# LJ_Mosfet_Power.net
KiCad netlist of a schematic drawn in Altium Designer
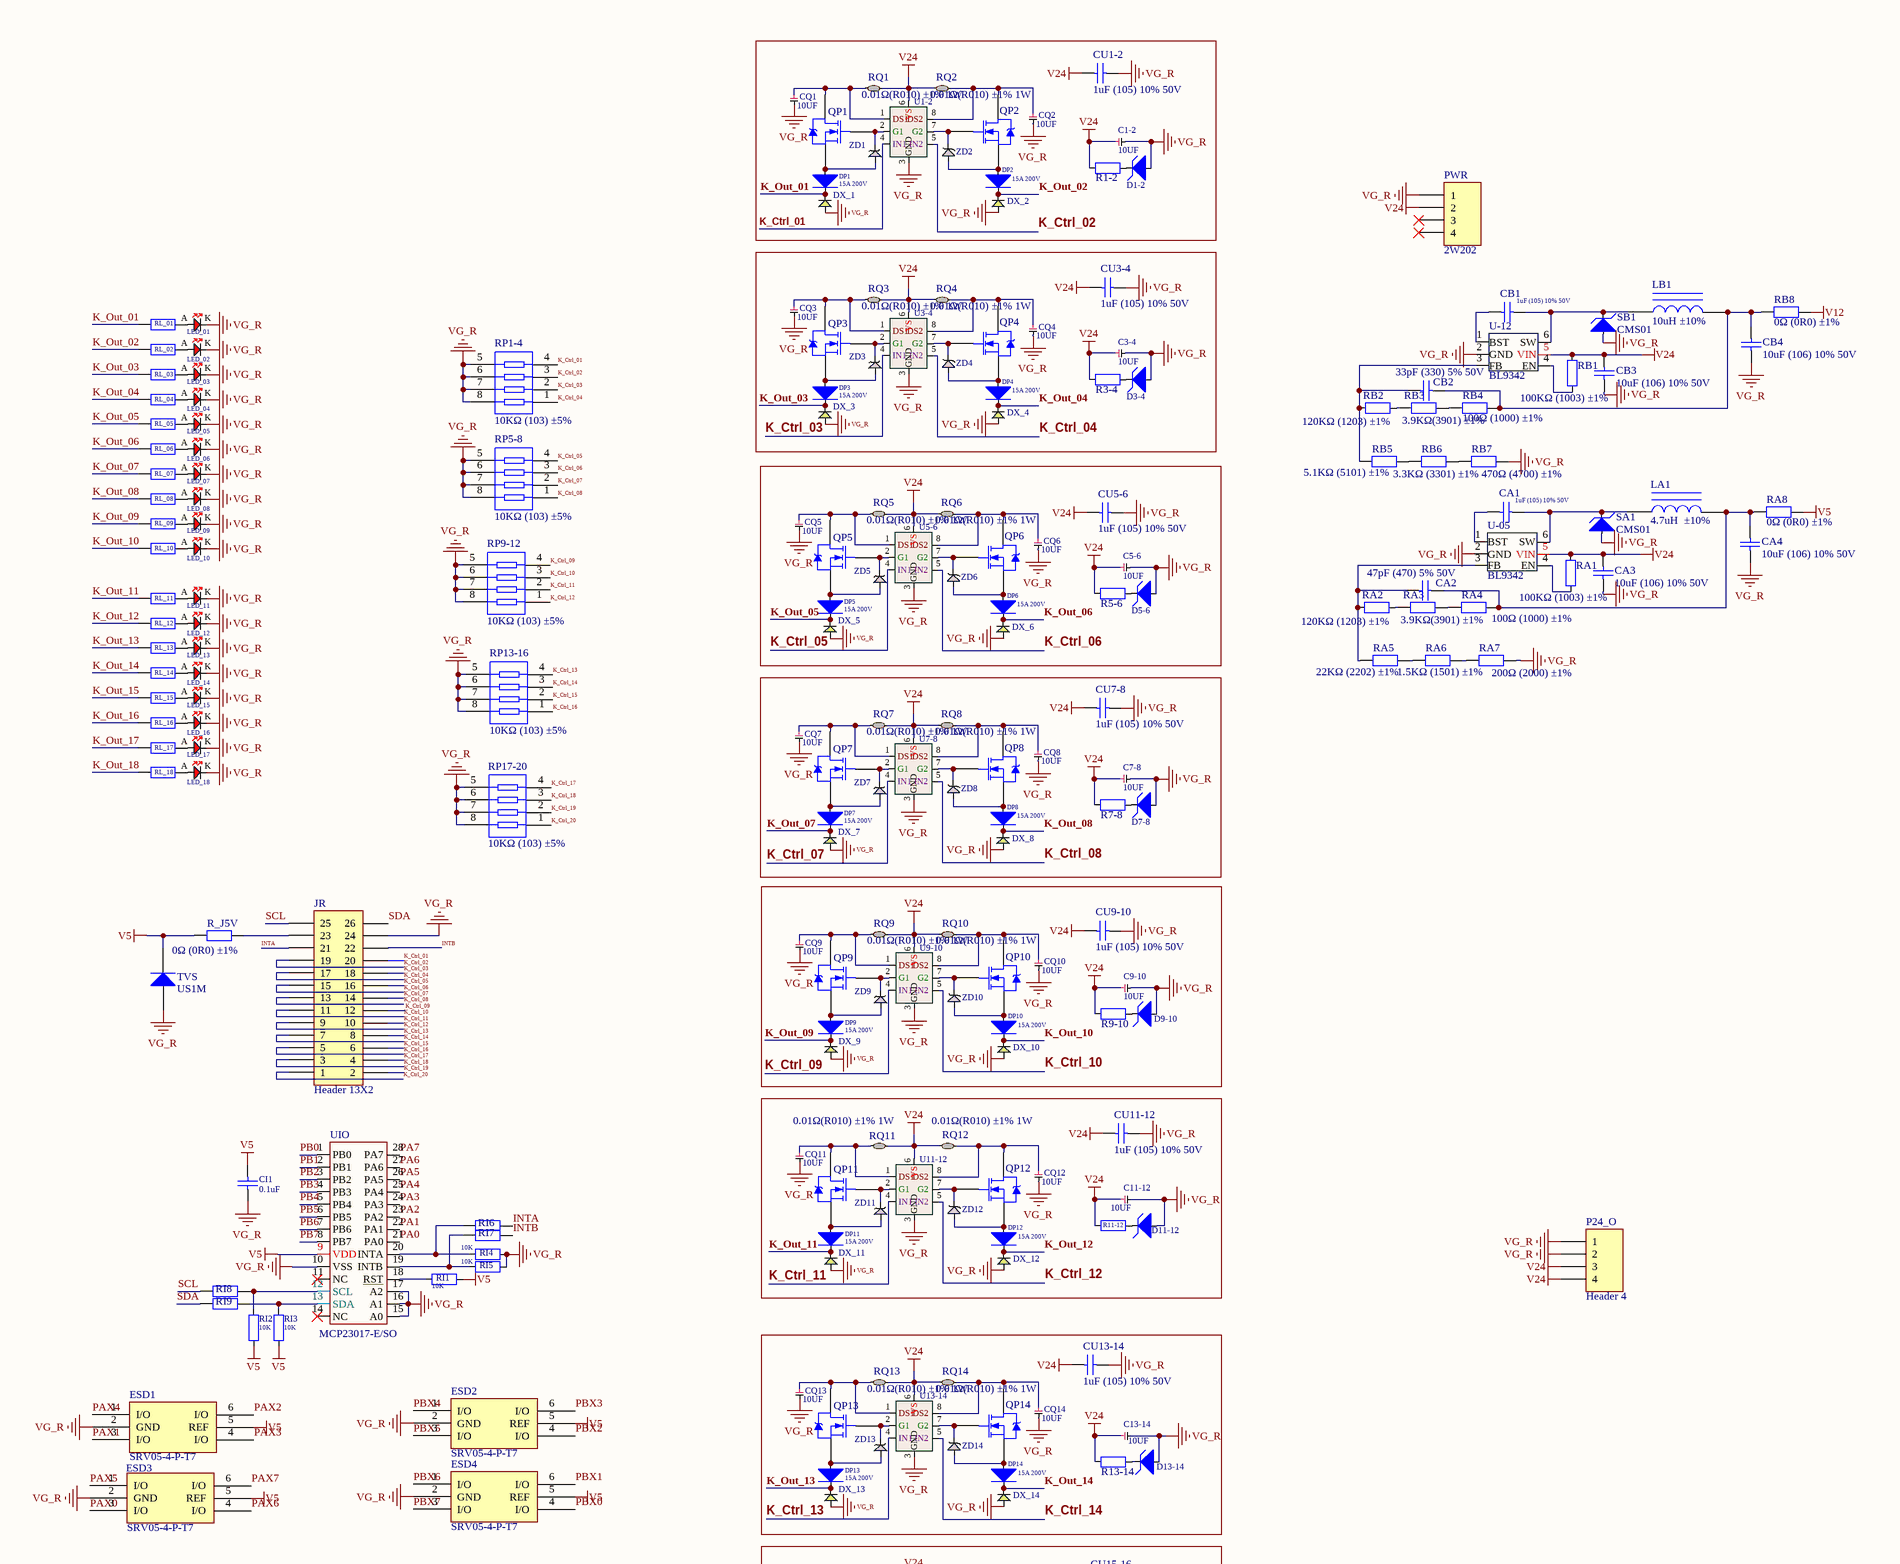
[diagram p0: LJ_Mosfet_Power.SchDoc, top left]
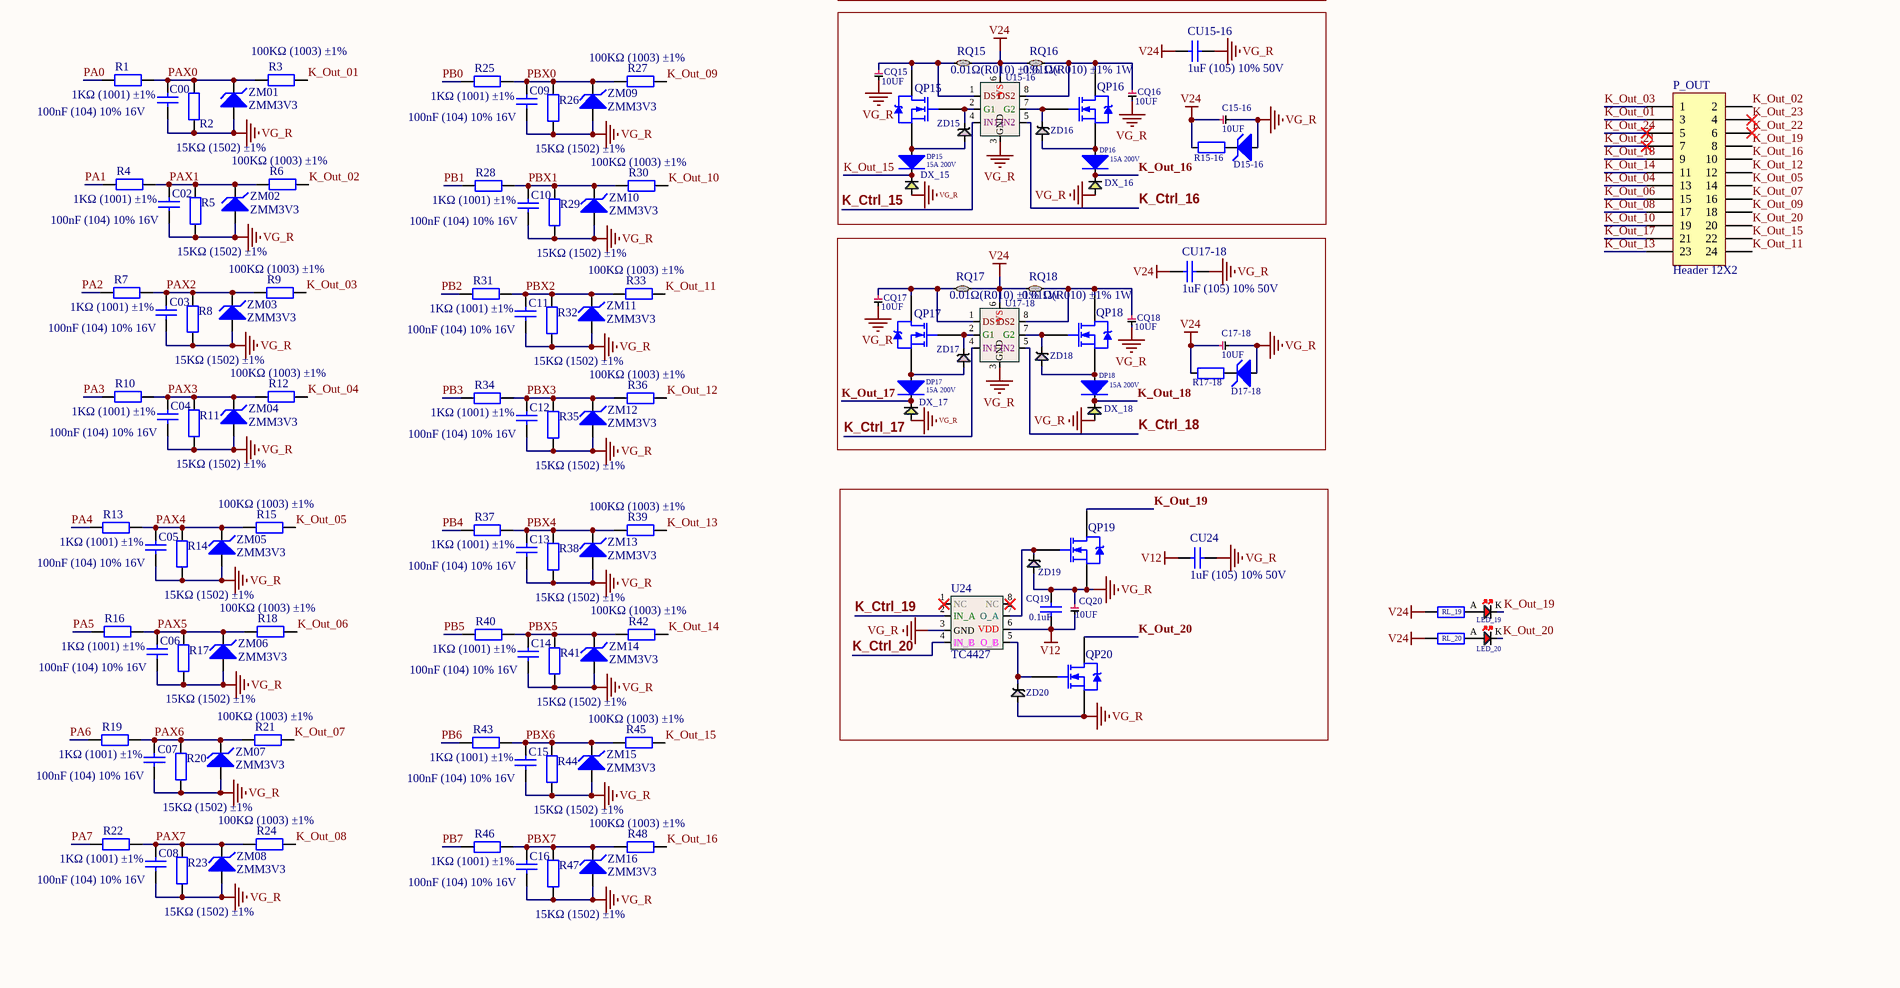
[diagram p1: LJ_Mosfet_Power.SchDoc, bottom left]
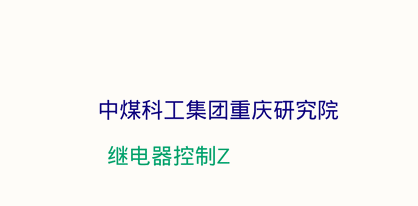
[diagram p2: LJ_Mosfet_Power.SchDoc, bottom right]

(export (version "E")
  (design (tool "Eeschema 10.0.6"))
  (components
    (comp (ref "C00")
      (value "100nF (104) 10% 16V")
      (footprint "0402_C")
      (description "贴片电容")
      (libsource (lib "Miscellaneous Devices LC") (part "0402 100nF (104) 10% 16V"))
    )
    (comp (ref "C1-2")
      (value "10UF")
      (footprint "C1210")
      (description "贴片电容")
      (libsource (lib "Active_crystal") (part "C"))
    )
    (comp (ref "C02")
      (value "100nF (104) 10% 16V")
      (footprint "0402_C")
      (description "贴片电容")
      (libsource (lib "Miscellaneous Devices LC") (part "0402 100nF (104) 10% 16V"))
    )
    (comp (ref "C03")
      (value "100nF (104) 10% 16V")
      (footprint "0402_C")
      (description "贴片电容")
      (libsource (lib "Miscellaneous Devices LC") (part "0402 100nF (104) 10% 16V"))
    )
    (comp (ref "C3-4")
      (value "10UF")
      (footprint "C1210")
      (description "贴片电容")
      (libsource (lib "Active_crystal") (part "C"))
    )
    (comp (ref "C04")
      (value "100nF (104) 10% 16V")
      (footprint "0402_C")
      (description "贴片电容")
      (libsource (lib "Miscellaneous Devices LC") (part "0402 100nF (104) 10% 16V"))
    )
    (comp (ref "C05")
      (value "100nF (104) 10% 16V")
      (footprint "0402_C")
      (description "贴片电容")
      (libsource (lib "Miscellaneous Devices LC") (part "0402 100nF (104) 10% 16V"))
    )
    (comp (ref "C5-6")
      (value "10UF")
      (footprint "C1210")
      (description "贴片电容")
      (libsource (lib "Active_crystal") (part "C"))
    )
    (comp (ref "C06")
      (value "100nF (104) 10% 16V")
      (footprint "0402_C")
      (description "贴片电容")
      (libsource (lib "Miscellaneous Devices LC") (part "0402 100nF (104) 10% 16V"))
    )
    (comp (ref "C07")
      (value "100nF (104) 10% 16V")
      (footprint "0402_C")
      (description "贴片电容")
      (libsource (lib "Miscellaneous Devices LC") (part "0402 100nF (104) 10% 16V"))
    )
    (comp (ref "C7-8")
      (value "10UF")
      (footprint "C1210")
      (description "贴片电容")
      (libsource (lib "Active_crystal") (part "C"))
    )
    (comp (ref "C08")
      (value "100nF (104) 10% 16V")
      (footprint "0402_C")
      (description "贴片电容")
      (libsource (lib "Miscellaneous Devices LC") (part "0402 100nF (104) 10% 16V"))
    )
    (comp (ref "C09")
      (value "100nF (104) 10% 16V")
      (footprint "0402_C")
      (description "贴片电容")
      (libsource (lib "Miscellaneous Devices LC") (part "0402 100nF (104) 10% 16V"))
    )
    (comp (ref "C9-10")
      (value "10UF")
      (footprint "C1210")
      (description "贴片电容")
      (libsource (lib "Active_crystal") (part "C"))
    )
    (comp (ref "C10")
      (value "100nF (104) 10% 16V")
      (footprint "0402_C")
      (description "贴片电容")
      (libsource (lib "Miscellaneous Devices LC") (part "0402 100nF (104) 10% 16V"))
    )
    (comp (ref "C11")
      (value "100nF (104) 10% 16V")
      (footprint "0402_C")
      (description "贴片电容")
      (libsource (lib "Miscellaneous Devices LC") (part "0402 100nF (104) 10% 16V"))
    )
    (comp (ref "C11-12")
      (value "10UF")
      (footprint "C1210")
      (description "贴片电容")
      (libsource (lib "Active_crystal") (part "C"))
    )
    (comp (ref "C12")
      (value "100nF (104) 10% 16V")
      (footprint "0402_C")
      (description "贴片电容")
      (libsource (lib "Miscellaneous Devices LC") (part "0402 100nF (104) 10% 16V"))
    )
    (comp (ref "C13")
      (value "100nF (104) 10% 16V")
      (footprint "0402_C")
      (description "贴片电容")
      (libsource (lib "Miscellaneous Devices LC") (part "0402 100nF (104) 10% 16V"))
    )
    (comp (ref "C13-14")
      (value "10UF")
      (footprint "C1210")
      (description "贴片电容")
      (libsource (lib "Active_crystal") (part "C"))
    )
    (comp (ref "C14")
      (value "100nF (104) 10% 16V")
      (footprint "0402_C")
      (description "贴片电容")
      (libsource (lib "Miscellaneous Devices LC") (part "0402 100nF (104) 10% 16V"))
    )
    (comp (ref "C15")
      (value "100nF (104) 10% 16V")
      (footprint "0402_C")
      (description "贴片电容")
      (libsource (lib "Miscellaneous Devices LC") (part "0402 100nF (104) 10% 16V"))
    )
    (comp (ref "C15-16")
      (value "10UF")
      (footprint "C1210")
      (description "贴片电容")
      (libsource (lib "Active_crystal") (part "C"))
    )
    (comp (ref "C16")
      (value "100nF (104) 10% 16V")
      (footprint "0402_C")
      (description "贴片电容")
      (libsource (lib "Miscellaneous Devices LC") (part "0402 100nF (104) 10% 16V"))
    )
    (comp (ref "C17-18")
      (value "10UF")
      (footprint "C1210")
      (description "贴片电容")
      (libsource (lib "Active_crystal") (part "C"))
    )
    (comp (ref "CA1")
      (value "1uF (105) 10% 50V")
      (footprint "0603_C")
      (description "贴片电容")
      (libsource (lib "LJ_Mosfet_Power") (part "0603 1uF (105) 10% 50V"))
    )
    (comp (ref "CA2")
      (value "47pF (470) 5% 50V")
      (footprint "0402_C")
      (description "贴片电容")
      (libsource (lib "Miscellaneous Devices LC") (part "0402 47pF (470) 5% 50V"))
    )
    (comp (ref "CA3")
      (value "10uF (106) 10% 50V")
      (footprint "1206_C")
      (description "贴片电容")
      (libsource (lib "Miscellaneous Devices LC") (part "1206 10uF (106) 10% 50V"))
    )
    (comp (ref "CA4")
      (value "10uF (106) 10% 50V")
      (footprint "1206_C")
      (description "贴片电容")
      (libsource (lib "Miscellaneous Devices LC") (part "1206 10uF (106) 10% 50V"))
    )
    (comp (ref "CB1")
      (value "1uF (105) 10% 50V")
      (footprint "0603_C")
      (description "贴片电容")
      (libsource (lib "LJ_Mosfet_Power") (part "0603 1uF (105) 10% 50V"))
    )
    (comp (ref "CB2")
      (value "33pF (330) 5% 50V")
      (footprint "0402_C")
      (description "贴片电容")
      (libsource (lib "Miscellaneous Devices LC") (part "0402 33pF (330) 5% 50V"))
    )
    (comp (ref "CB3")
      (value "10uF (106) 10% 50V")
      (footprint "1206_C")
      (description "贴片电容")
      (libsource (lib "Miscellaneous Devices LC") (part "1206 10uF (106) 10% 50V"))
    )
    (comp (ref "CB4")
      (value "10uF (106) 10% 50V")
      (footprint "1206_C")
      (description "贴片电容")
      (libsource (lib "Miscellaneous Devices LC") (part "1206 10uF (106) 10% 50V"))
    )
    (comp (ref "CI1")
      (value "100nF (104) 10% 50V")
      (footprint "0603_C")
      (description "贴片电容")
      (fields (field (name "VAL") "0.1uF"))
      (libsource (lib "LJ_Mosfet_Power") (part "0603 100nF (104) 10% 50V"))
    )
    (comp (ref "CQ1") (value "10UF") (footprint "C1210") (libsource (lib "Active_crystal") (part "C")))
    (comp (ref "CQ2") (value "10UF") (footprint "C1210") (libsource (lib "Active_crystal") (part "C")))
    (comp (ref "CQ3") (value "10UF") (footprint "C1210") (libsource (lib "Active_crystal") (part "C")))
    (comp (ref "CQ4") (value "10UF") (footprint "C1210") (libsource (lib "Active_crystal") (part "C")))
    (comp (ref "CQ5") (value "10UF") (footprint "C1210") (libsource (lib "Active_crystal") (part "C")))
    (comp (ref "CQ6") (value "10UF") (footprint "C1210") (libsource (lib "Active_crystal") (part "C")))
    (comp (ref "CQ7") (value "10UF") (footprint "C1210") (libsource (lib "Active_crystal") (part "C")))
    (comp (ref "CQ8") (value "10UF") (footprint "C1210") (libsource (lib "Active_crystal") (part "C")))
    (comp (ref "CQ9") (value "10UF") (footprint "C1210") (libsource (lib "Active_crystal") (part "C")))
    (comp (ref "CQ10") (value "10UF") (footprint "C1210") (libsource (lib "Active_crystal") (part "C")))
    (comp (ref "CQ11") (value "10UF") (footprint "C1210") (libsource (lib "Active_crystal") (part "C")))
    (comp (ref "CQ12") (value "10UF") (footprint "C1210") (libsource (lib "Active_crystal") (part "C")))
    (comp (ref "CQ13") (value "10UF") (footprint "C1210") (libsource (lib "Active_crystal") (part "C")))
    (comp (ref "CQ14") (value "10UF") (footprint "C1210") (libsource (lib "Active_crystal") (part "C")))
    (comp (ref "CQ15") (value "10UF") (footprint "C1210") (libsource (lib "Active_crystal") (part "C")))
    (comp (ref "CQ16") (value "10UF") (footprint "C1210") (libsource (lib "Active_crystal") (part "C")))
    (comp (ref "CQ17") (value "10UF") (footprint "C1210") (libsource (lib "Active_crystal") (part "C")))
    (comp (ref "CQ18") (value "10UF") (footprint "C1210") (libsource (lib "Active_crystal") (part "C")))
    (comp (ref "CQ19")
      (value "100nF (104) 10% 50V")
      (footprint "0603_C")
      (description "贴片电容")
      (fields (field (name "VAL") "0.1uF"))
      (libsource (lib "Miscellaneous Devices LC") (part "0603 100nF (104) 10% 50V"))
    )
    (comp (ref "CQ20")
      (value "10UF")
      (footprint "C1210")
      (description "贴片电容")
      (libsource (lib "Active_crystal") (part "C"))
    )
    (comp (ref "CU1-2")
      (value "1uF (105) 10% 50V")
      (footprint "0805_C")
      (description "贴片电容")
      (libsource (lib "Miscellaneous Devices LC") (part "0805 1uF (105) 10% 50V"))
    )
    (comp (ref "CU3-4")
      (value "1uF (105) 10% 50V")
      (footprint "0805_C")
      (description "贴片电容")
      (libsource (lib "Miscellaneous Devices LC") (part "0805 1uF (105) 10% 50V"))
    )
    (comp (ref "CU5-6")
      (value "1uF (105) 10% 50V")
      (footprint "0805_C")
      (description "贴片电容")
      (libsource (lib "Miscellaneous Devices LC") (part "0805 1uF (105) 10% 50V"))
    )
    (comp (ref "CU7-8")
      (value "1uF (105) 10% 50V")
      (footprint "0805_C")
      (description "贴片电容")
      (libsource (lib "Miscellaneous Devices LC") (part "0805 1uF (105) 10% 50V"))
    )
    (comp (ref "CU9-10")
      (value "1uF (105) 10% 50V")
      (footprint "0805_C")
      (description "贴片电容")
      (libsource (lib "Miscellaneous Devices LC") (part "0805 1uF (105) 10% 50V"))
    )
    (comp (ref "CU11-12")
      (value "1uF (105) 10% 50V")
      (footprint "0805_C")
      (description "贴片电容")
      (libsource (lib "Miscellaneous Devices LC") (part "0805 1uF (105) 10% 50V"))
    )
    (comp (ref "CU13-14")
      (value "1uF (105) 10% 50V")
      (footprint "0805_C")
      (description "贴片电容")
      (libsource (lib "Miscellaneous Devices LC") (part "0805 1uF (105) 10% 50V"))
    )
    (comp (ref "CU15-16")
      (value "1uF (105) 10% 50V")
      (footprint "0805_C")
      (description "贴片电容")
      (libsource (lib "Miscellaneous Devices LC") (part "0805 1uF (105) 10% 50V"))
    )
    (comp (ref "CU17-18")
      (value "1uF (105) 10% 50V")
      (footprint "0805_C")
      (description "贴片电容")
      (libsource (lib "Miscellaneous Devices LC") (part "0805 1uF (105) 10% 50V"))
    )
    (comp (ref "CU24")
      (value "1uF (105) 10% 50V")
      (footprint "0805_C")
      (description "贴片电容")
      (libsource (lib "Miscellaneous Devices LC") (part "0805 1uF (105) 10% 50V"))
    )
    (comp (ref "D1-2")
      (value "ZMM5255B")
      (footprint "LL-34")
      (description "稳压二极管")
      (libsource (lib "Miscellaneous Devices LC") (part "LL-34 ZMM5V6"))
    )
    (comp (ref "D3-4")
      (value "ZMM5255B")
      (footprint "LL-34")
      (description "稳压二极管")
      (libsource (lib "Miscellaneous Devices LC") (part "LL-34 ZMM5V6"))
    )
    (comp (ref "D5-6")
      (value "ZMM5255B")
      (footprint "LL-34")
      (description "稳压二极管")
      (libsource (lib "Miscellaneous Devices LC") (part "LL-34 ZMM5V6"))
    )
    (comp (ref "D7-8")
      (value "ZMM5255B")
      (footprint "LL-34")
      (description "稳压二极管")
      (libsource (lib "Miscellaneous Devices LC") (part "LL-34 ZMM5V6"))
    )
    (comp (ref "D9-10")
      (value "ZMM5255B")
      (footprint "LL-34")
      (description "稳压二极管")
      (libsource (lib "Miscellaneous Devices LC") (part "LL-34 ZMM5V6"))
    )
    (comp (ref "D11-12")
      (value "ZMM5255B")
      (footprint "LL-34")
      (description "稳压二极管")
      (libsource (lib "Miscellaneous Devices LC") (part "LL-34 ZMM5V6"))
    )
    (comp (ref "D13-14")
      (value "ZMM5255B")
      (footprint "LL-34")
      (description "稳压二极管")
      (libsource (lib "Miscellaneous Devices LC") (part "LL-34 ZMM5V6"))
    )
    (comp (ref "D15-16")
      (value "ZMM5255B")
      (footprint "LL-34")
      (description "稳压二极管")
      (libsource (lib "Miscellaneous Devices LC") (part "LL-34 ZMM5V6"))
    )
    (comp (ref "D17-18")
      (value "ZMM5255B")
      (footprint "LL-34")
      (description "稳压二极管")
      (libsource (lib "Miscellaneous Devices LC") (part "LL-34 ZMM5V6"))
    )
    (comp (ref "DP1")
      (value "15A 200V")
      (footprint "TO-277B")
      (description "SB1045L-TO-277超低功耗肖特基二极管")
      (libsource (lib "Miscellaneous Devices") (part "Diode"))
    )
    (comp (ref "DP2")
      (value "15A 200V")
      (footprint "TO-277B")
      (description "SB1045L-TO-277超低功耗肖特基二极管")
      (libsource (lib "Miscellaneous Devices") (part "Diode"))
    )
    (comp (ref "DP3")
      (value "15A 200V")
      (footprint "TO-277B")
      (description "SB1045L-TO-277超低功耗肖特基二极管")
      (libsource (lib "Miscellaneous Devices") (part "Diode"))
    )
    (comp (ref "DP4")
      (value "15A 200V")
      (footprint "TO-277B")
      (description "SB1045L-TO-277超低功耗肖特基二极管")
      (libsource (lib "Miscellaneous Devices") (part "Diode"))
    )
    (comp (ref "DP5")
      (value "15A 200V")
      (footprint "TO-277B")
      (description "SB1045L-TO-277超低功耗肖特基二极管")
      (libsource (lib "Miscellaneous Devices") (part "Diode"))
    )
    (comp (ref "DP6")
      (value "15A 200V")
      (footprint "TO-277B")
      (description "SB1045L-TO-277超低功耗肖特基二极管")
      (libsource (lib "Miscellaneous Devices") (part "Diode"))
    )
    (comp (ref "DP7")
      (value "15A 200V")
      (footprint "TO-277B")
      (description "SB1045L-TO-277超低功耗肖特基二极管")
      (libsource (lib "Miscellaneous Devices") (part "Diode"))
    )
    (comp (ref "DP8")
      (value "15A 200V")
      (footprint "TO-277B")
      (description "SB1045L-TO-277超低功耗肖特基二极管")
      (libsource (lib "Miscellaneous Devices") (part "Diode"))
    )
    (comp (ref "DP9")
      (value "15A 200V")
      (footprint "TO-277B")
      (description "SB1045L-TO-277超低功耗肖特基二极管")
      (libsource (lib "Miscellaneous Devices") (part "Diode"))
    )
    (comp (ref "DP10")
      (value "15A 200V")
      (footprint "TO-277B")
      (description "SB1045L-TO-277超低功耗肖特基二极管")
      (libsource (lib "Miscellaneous Devices") (part "Diode"))
    )
    (comp (ref "DP11")
      (value "15A 200V")
      (footprint "TO-277B")
      (description "SB1045L-TO-277超低功耗肖特基二极管")
      (libsource (lib "Miscellaneous Devices") (part "Diode"))
    )
    (comp (ref "DP12")
      (value "15A 200V")
      (footprint "TO-277B")
      (description "SB1045L-TO-277超低功耗肖特基二极管")
      (libsource (lib "Miscellaneous Devices") (part "Diode"))
    )
    (comp (ref "DP13")
      (value "15A 200V")
      (footprint "TO-277B")
      (description "SB1045L-TO-277超低功耗肖特基二极管")
      (libsource (lib "Miscellaneous Devices") (part "Diode"))
    )
    (comp (ref "DP14")
      (value "15A 200V")
      (footprint "TO-277B")
      (description "SB1045L-TO-277超低功耗肖特基二极管")
      (libsource (lib "Miscellaneous Devices") (part "Diode"))
    )
    (comp (ref "DP15")
      (value "15A 200V")
      (footprint "TO-277B")
      (description "SB1045L-TO-277超低功耗肖特基二极管")
      (libsource (lib "Miscellaneous Devices") (part "Diode"))
    )
    (comp (ref "DP16")
      (value "15A 200V")
      (footprint "TO-277B")
      (description "SB1045L-TO-277超低功耗肖特基二极管")
      (libsource (lib "Miscellaneous Devices") (part "Diode"))
    )
    (comp (ref "DP17")
      (value "15A 200V")
      (footprint "TO-277B")
      (description "SB1045L-TO-277超低功耗肖特基二极管")
      (libsource (lib "Miscellaneous Devices") (part "Diode"))
    )
    (comp (ref "DP18")
      (value "15A 200V")
      (footprint "TO-277B")
      (description "SB1045L-TO-277超低功耗肖特基二极管")
      (libsource (lib "Miscellaneous Devices") (part "Diode"))
    )
    (comp (ref "DX_1") (value "US5M") (footprint "SMC") (libsource (lib "Active_crystal") (part "D")))
    (comp (ref "DX_2") (value "US5M") (footprint "SMC") (libsource (lib "Active_crystal") (part "D")))
    (comp (ref "DX_3") (value "US5M") (footprint "SMC") (libsource (lib "Active_crystal") (part "D")))
    (comp (ref "DX_4") (value "US5M") (footprint "SMC") (libsource (lib "Active_crystal") (part "D")))
    (comp (ref "DX_5") (value "US5M") (footprint "SMC") (libsource (lib "Active_crystal") (part "D")))
    (comp (ref "DX_6") (value "US5M") (footprint "SMC") (libsource (lib "Active_crystal") (part "D")))
    (comp (ref "DX_7") (value "US5M") (footprint "SMC") (libsource (lib "Active_crystal") (part "D")))
    (comp (ref "DX_8") (value "US5M") (footprint "SMC") (libsource (lib "Active_crystal") (part "D")))
    (comp (ref "DX_9") (value "US5M") (footprint "SMC") (libsource (lib "Active_crystal") (part "D")))
    (comp (ref "DX_10") (value "US5M") (footprint "SMC") (libsource (lib "Active_crystal") (part "D")))
    (comp (ref "DX_11") (value "US5M") (footprint "SMC") (libsource (lib "Active_crystal") (part "D")))
    (comp (ref "DX_12") (value "US5M") (footprint "SMC") (libsource (lib "Active_crystal") (part "D")))
    (comp (ref "DX_13") (value "US5M") (footprint "SMC") (libsource (lib "Active_crystal") (part "D")))
    (comp (ref "DX_14") (value "US5M") (footprint "SMC") (libsource (lib "Active_crystal") (part "D")))
    (comp (ref "DX_15") (value "US5M") (footprint "SMC") (libsource (lib "Active_crystal") (part "D")))
    (comp (ref "DX_16") (value "US5M") (footprint "SMC") (libsource (lib "Active_crystal") (part "D")))
    (comp (ref "DX_17") (value "US5M") (footprint "SMC") (libsource (lib "Active_crystal") (part "D")))
    (comp (ref "DX_18")
      (value "US5M")
      (footprint "SMC")
      (description "超快恢复二极管")
      (libsource (lib "Active_crystal") (part "D"))
    )
    (comp (ref "ESD1")
      (value "SRV05-4-P-T7")
      (footprint "SOT23-6")
      (description "TVS")
      (libsource (lib "Miscellaneous Devices LC") (part "SRV05-4-P-T7_[C85364]"))
    )
    (comp (ref "ESD2")
      (value "SRV05-4-P-T7")
      (footprint "SOT23-6")
      (description "TVS")
      (libsource (lib "Miscellaneous Devices LC") (part "SRV05-4-P-T7_[C85364]"))
    )
    (comp (ref "ESD3")
      (value "SRV05-4-P-T7")
      (footprint "SOT23-6")
      (description "TVS")
      (libsource (lib "Miscellaneous Devices LC") (part "SRV05-4-P-T7_[C85364]"))
    )
    (comp (ref "ESD4")
      (value "SRV05-4-P-T7")
      (footprint "SOT23-6")
      (description "TVS")
      (libsource (lib "Miscellaneous Devices LC") (part "SRV05-4-P-T7_[C85364]"))
    )
    (comp (ref "JR")
      (value "Header 13X2")
      (footprint "FKV26HR")
      (description "Header, 13-Pin, Dual row")
      (libsource (lib "Miscellaneous Connectors") (part "Header 13X2"))
    )
    (comp (ref "LA1")
      (value "4.7uH  ±10%")
      (footprint "1206_L")
      (description "贴片电感")
      (libsource (lib "Miscellaneous Devices LC") (part "1206 4.7uH  10%"))
    )
    (comp (ref "LB1")
      (value "10uH ±10%")
      (footprint "1206_L")
      (description "贴片电感")
      (libsource (lib "Miscellaneous Devices LC") (part "1206 10uH 10%"))
    )
    (comp (ref "LED_01")
      (value "红灯 0603")
      (footprint "0603_LED_S1")
      (description "发光二极管")
      (libsource (lib "Active_crystal") (part "LED_R"))
    )
    (comp (ref "LED_02")
      (value "红灯 0603")
      (footprint "0603_LED_S1")
      (description "发光二极管")
      (libsource (lib "Active_crystal") (part "LED_R"))
    )
    (comp (ref "LED_03")
      (value "红灯 0603")
      (footprint "0603_LED_S1")
      (description "发光二极管")
      (libsource (lib "Active_crystal") (part "LED_R"))
    )
    (comp (ref "LED_04")
      (value "红灯 0603")
      (footprint "0603_LED_S1")
      (description "发光二极管")
      (libsource (lib "Active_crystal") (part "LED_R"))
    )
    (comp (ref "LED_05")
      (value "红灯 0603")
      (footprint "0603_LED_S1")
      (description "发光二极管")
      (libsource (lib "Active_crystal") (part "LED_R"))
    )
    (comp (ref "LED_06")
      (value "红灯 0603")
      (footprint "0603_LED_S1")
      (description "发光二极管")
      (libsource (lib "Active_crystal") (part "LED_R"))
    )
    (comp (ref "LED_07")
      (value "红灯 0603")
      (footprint "0603_LED_S1")
      (description "发光二极管")
      (libsource (lib "Active_crystal") (part "LED_R"))
    )
    (comp (ref "LED_08")
      (value "红灯 0603")
      (footprint "0603_LED_S1")
      (description "发光二极管")
      (libsource (lib "Active_crystal") (part "LED_R"))
    )
    (comp (ref "LED_09")
      (value "红灯 0603")
      (footprint "0603_LED_S1")
      (description "发光二极管")
      (libsource (lib "Active_crystal") (part "LED_R"))
    )
    (comp (ref "LED_10")
      (value "红灯 0603")
      (footprint "0603_LED_S1")
      (description "发光二极管")
      (libsource (lib "Active_crystal") (part "LED_R"))
    )
    (comp (ref "LED_11")
      (value "红灯 0603")
      (footprint "0603_LED_S1")
      (description "发光二极管")
      (libsource (lib "Active_crystal") (part "LED_R"))
    )
    (comp (ref "LED_12")
      (value "红灯 0603")
      (footprint "0603_LED_S1")
      (description "发光二极管")
      (libsource (lib "Active_crystal") (part "LED_R"))
    )
    (comp (ref "LED_13")
      (value "红灯 0603")
      (footprint "0603_LED_S1")
      (description "发光二极管")
      (libsource (lib "Active_crystal") (part "LED_R"))
    )
    (comp (ref "LED_14")
      (value "红灯 0603")
      (footprint "0603_LED_S1")
      (description "发光二极管")
      (libsource (lib "Active_crystal") (part "LED_R"))
    )
    (comp (ref "LED_15")
      (value "红灯 0603")
      (footprint "0603_LED_S1")
      (description "发光二极管")
      (libsource (lib "Active_crystal") (part "LED_R"))
    )
    (comp (ref "LED_16")
      (value "红灯 0603")
      (footprint "0603_LED_S1")
      (description "发光二极管")
      (libsource (lib "Active_crystal") (part "LED_R"))
    )
    (comp (ref "LED_17")
      (value "红灯 0603")
      (footprint "0603_LED_S1")
      (description "发光二极管")
      (libsource (lib "Active_crystal") (part "LED_R"))
    )
    (comp (ref "LED_18")
      (value "红灯 0603")
      (footprint "0603_LED_S1")
      (description "发光二极管")
      (libsource (lib "Active_crystal") (part "LED_R"))
    )
    (comp (ref "LED_19")
      (value "红灯 0603")
      (footprint "0603_LED_S1")
      (description "发光二极管")
      (libsource (lib "Active_crystal") (part "LED_R"))
    )
    (comp (ref "LED_20")
      (value "红灯 0603")
      (footprint "0603_LED_S1")
      (description "发光二极管")
      (libsource (lib "Active_crystal") (part "LED_R"))
    )
    (comp (ref "P24_O")
      (value "Header 4")
      (footprint "KF235-5.0-4P")
      (description "Header, 4-Pin")
      (fields (field (name "PUBLISHER") "Altium Limited"))
      (libsource (lib "Miscellaneous Connectors") (part "Header 4"))
    )
    (comp (ref "PWR")
      (value "2W202")
      (footprint "2W2公90度带支架锁螺丝")
      (description "2W2公90度带支架锁螺丝")
      (libsource (lib "Miscellaneous Connectors") (part "Header 4"))
    )
    (comp (ref "P_OUT")
      (value "Header 12X2")
      (footprint "5569_24P")
      (description "Header, 12-Pin, Dual row")
      (libsource (lib "Miscellaneous Connectors") (part "Header 12X2"))
    )
    (comp (ref "QP1")
      (value "STB120NF10")
      (footprint "DPAK2 /to263")
      (description "N-Channel Power MOSFET")
      (libsource (lib "Miscellaneous Devices") (part "NMOS-2"))
    )
    (comp (ref "QP2")
      (value "STB120NF10")
      (footprint "DPAK2 /to263")
      (description "N-Channel Power MOSFET")
      (libsource (lib "Miscellaneous Devices") (part "NMOS-2"))
    )
    (comp (ref "QP3")
      (value "STB120NF10")
      (footprint "DPAK2 /to263")
      (description "N-Channel Power MOSFET")
      (libsource (lib "Miscellaneous Devices") (part "NMOS-2"))
    )
    (comp (ref "QP4")
      (value "STB120NF10")
      (footprint "DPAK2 /to263")
      (description "N-Channel Power MOSFET")
      (libsource (lib "Miscellaneous Devices") (part "NMOS-2"))
    )
    (comp (ref "QP5")
      (value "STB120NF10")
      (footprint "DPAK2 /to263")
      (description "N-Channel Power MOSFET")
      (libsource (lib "Miscellaneous Devices") (part "NMOS-2"))
    )
    (comp (ref "QP6")
      (value "STB120NF10")
      (footprint "DPAK2 /to263")
      (description "N-Channel Power MOSFET")
      (libsource (lib "Miscellaneous Devices") (part "NMOS-2"))
    )
    (comp (ref "QP7")
      (value "STB120NF10")
      (footprint "DPAK2 /to263")
      (description "N-Channel Power MOSFET")
      (libsource (lib "Miscellaneous Devices") (part "NMOS-2"))
    )
    (comp (ref "QP8")
      (value "STB120NF10")
      (footprint "DPAK2 /to263")
      (description "N-Channel Power MOSFET")
      (libsource (lib "Miscellaneous Devices") (part "NMOS-2"))
    )
    (comp (ref "QP9")
      (value "STB120NF10")
      (footprint "DPAK2 /to263")
      (description "N-Channel Power MOSFET")
      (libsource (lib "Miscellaneous Devices") (part "NMOS-2"))
    )
    (comp (ref "QP10")
      (value "STB120NF10")
      (footprint "DPAK2 /to263")
      (description "N-Channel Power MOSFET")
      (libsource (lib "Miscellaneous Devices") (part "NMOS-2"))
    )
    (comp (ref "QP11")
      (value "STB120NF10")
      (footprint "DPAK2 /to263")
      (description "N-Channel Power MOSFET")
      (libsource (lib "Miscellaneous Devices") (part "NMOS-2"))
    )
    (comp (ref "QP12")
      (value "STB120NF10")
      (footprint "DPAK2 /to263")
      (description "N-Channel Power MOSFET")
      (libsource (lib "Miscellaneous Devices") (part "NMOS-2"))
    )
    (comp (ref "QP13")
      (value "STB120NF10")
      (footprint "DPAK2 /to263")
      (description "N-Channel Power MOSFET")
      (libsource (lib "Miscellaneous Devices") (part "NMOS-2"))
    )
    (comp (ref "QP14")
      (value "STB120NF10")
      (footprint "DPAK2 /to263")
      (description "N-Channel Power MOSFET")
      (libsource (lib "Miscellaneous Devices") (part "NMOS-2"))
    )
    (comp (ref "QP15")
      (value "STB120NF10")
      (footprint "DPAK2 /to263")
      (description "N-Channel Power MOSFET")
      (libsource (lib "Miscellaneous Devices") (part "NMOS-2"))
    )
    (comp (ref "QP16")
      (value "STB120NF10")
      (footprint "DPAK2 /to263")
      (description "N-Channel Power MOSFET")
      (libsource (lib "Miscellaneous Devices") (part "NMOS-2"))
    )
    (comp (ref "QP17")
      (value "STB120NF10")
      (footprint "DPAK2 /to263")
      (description "N-Channel Power MOSFET")
      (libsource (lib "Miscellaneous Devices") (part "NMOS-2"))
    )
    (comp (ref "QP18")
      (value "STB120NF10")
      (footprint "DPAK2 /to263")
      (description "N-Channel Power MOSFET")
      (libsource (lib "Miscellaneous Devices") (part "NMOS-2"))
    )
    (comp (ref "QP19")
      (value "STB120NF10")
      (footprint "DPAK2 /to263")
      (description "N-Channel Power MOSFET")
      (libsource (lib "Miscellaneous Devices") (part "NMOS-2"))
    )
    (comp (ref "QP20")
      (value "STB120NF10")
      (footprint "DPAK2 /to263")
      (description "N-Channel Power MOSFET")
      (libsource (lib "Miscellaneous Devices") (part "NMOS-2"))
    )
    (comp (ref "R1")
      (value "1KΩ (1001) ±1%")
      (footprint "0402_R")
      (description "贴片电阻")
      (libsource (lib "Miscellaneous Devices LC") (part "0402 1KΩ (1001) 1%"))
    )
    (comp (ref "R1-2")
      (value "1KΩ (1001) ±1%")
      (footprint "0805_R")
      (description "贴片电阻")
      (libsource (lib "Miscellaneous Devices LC") (part "0805 1KΩ (1001) 1%"))
    )
    (comp (ref "R2")
      (value "15KΩ (1502) ±1%")
      (footprint "0402_R")
      (description "贴片电阻")
      (libsource (lib "Miscellaneous Devices LC") (part "0402 15KΩ (1502) 1%"))
    )
    (comp (ref "R3")
      (value "100KΩ (1003) ±1%")
      (footprint "0402_R")
      (description "贴片电阻")
      (libsource (lib "Miscellaneous Devices LC") (part "0402 100KΩ (1003) 1%"))
    )
    (comp (ref "R3-4")
      (value "1KΩ (1001) ±1%")
      (footprint "0805_R")
      (description "贴片电阻")
      (libsource (lib "Miscellaneous Devices LC") (part "0805 1KΩ (1001) 1%"))
    )
    (comp (ref "R4")
      (value "1KΩ (1001) ±1%")
      (footprint "0402_R")
      (description "贴片电阻")
      (libsource (lib "Miscellaneous Devices LC") (part "0402 1KΩ (1001) 1%"))
    )
    (comp (ref "R5")
      (value "15KΩ (1502) ±1%")
      (footprint "0402_R")
      (description "贴片电阻")
      (libsource (lib "Miscellaneous Devices LC") (part "0402 15KΩ (1502) 1%"))
    )
    (comp (ref "R5-6")
      (value "1KΩ (1001) ±1%")
      (footprint "0805_R")
      (description "贴片电阻")
      (libsource (lib "Miscellaneous Devices LC") (part "0805 1KΩ (1001) 1%"))
    )
    (comp (ref "R6")
      (value "100KΩ (1003) ±1%")
      (footprint "0402_R")
      (description "贴片电阻")
      (libsource (lib "Miscellaneous Devices LC") (part "0402 100KΩ (1003) 1%"))
    )
    (comp (ref "R7")
      (value "1KΩ (1001) ±1%")
      (footprint "0402_R")
      (description "贴片电阻")
      (libsource (lib "Miscellaneous Devices LC") (part "0402 1KΩ (1001) 1%"))
    )
    (comp (ref "R7-8")
      (value "1KΩ (1001) ±1%")
      (footprint "0805_R")
      (description "贴片电阻")
      (libsource (lib "Miscellaneous Devices LC") (part "0805 1KΩ (1001) 1%"))
    )
    (comp (ref "R8")
      (value "15KΩ (1502) ±1%")
      (footprint "0402_R")
      (description "贴片电阻")
      (libsource (lib "Miscellaneous Devices LC") (part "0402 15KΩ (1502) 1%"))
    )
    (comp (ref "R9")
      (value "100KΩ (1003) ±1%")
      (footprint "0402_R")
      (description "贴片电阻")
      (libsource (lib "Miscellaneous Devices LC") (part "0402 100KΩ (1003) 1%"))
    )
    (comp (ref "R9-10")
      (value "1KΩ (1001) ±1%")
      (footprint "0805_R")
      (description "贴片电阻")
      (libsource (lib "Miscellaneous Devices LC") (part "0805 1KΩ (1001) 1%"))
    )
    (comp (ref "R10")
      (value "1KΩ (1001) ±1%")
      (footprint "0402_R")
      (description "贴片电阻")
      (libsource (lib "Miscellaneous Devices LC") (part "0402 1KΩ (1001) 1%"))
    )
    (comp (ref "R11")
      (value "15KΩ (1502) ±1%")
      (footprint "0402_R")
      (description "贴片电阻")
      (libsource (lib "Miscellaneous Devices LC") (part "0402 15KΩ (1502) 1%"))
    )
    (comp (ref "R11-12")
      (value "1KΩ (1001) ±1%")
      (footprint "0805_R")
      (description "贴片电阻")
      (libsource (lib "Miscellaneous Devices LC") (part "0805 1KΩ (1001) 1%"))
    )
    (comp (ref "R12")
      (value "100KΩ (1003) ±1%")
      (footprint "0402_R")
      (description "贴片电阻")
      (libsource (lib "Miscellaneous Devices LC") (part "0402 100KΩ (1003) 1%"))
    )
    (comp (ref "R13")
      (value "1KΩ (1001) ±1%")
      (footprint "0402_R")
      (description "贴片电阻")
      (libsource (lib "Miscellaneous Devices LC") (part "0402 1KΩ (1001) 1%"))
    )
    (comp (ref "R13-14")
      (value "1KΩ (1001) ±1%")
      (footprint "0805_R")
      (description "贴片电阻")
      (libsource (lib "Miscellaneous Devices LC") (part "0805 1KΩ (1001) 1%"))
    )
    (comp (ref "R14")
      (value "15KΩ (1502) ±1%")
      (footprint "0402_R")
      (description "贴片电阻")
      (libsource (lib "Miscellaneous Devices LC") (part "0402 15KΩ (1502) 1%"))
    )
    (comp (ref "R15")
      (value "100KΩ (1003) ±1%")
      (footprint "0402_R")
      (description "贴片电阻")
      (libsource (lib "Miscellaneous Devices LC") (part "0402 100KΩ (1003) 1%"))
    )
    (comp (ref "R15-16")
      (value "1KΩ (1001) ±1%")
      (footprint "0805_R")
      (description "贴片电阻")
      (libsource (lib "Miscellaneous Devices LC") (part "0805 1KΩ (1001) 1%"))
    )
    (comp (ref "R16")
      (value "1KΩ (1001) ±1%")
      (footprint "0402_R")
      (description "贴片电阻")
      (libsource (lib "Miscellaneous Devices LC") (part "0402 1KΩ (1001) 1%"))
    )
    (comp (ref "R17")
      (value "15KΩ (1502) ±1%")
      (footprint "0402_R")
      (description "贴片电阻")
      (libsource (lib "Miscellaneous Devices LC") (part "0402 15KΩ (1502) 1%"))
    )
    (comp (ref "R17-18")
      (value "1KΩ (1001) ±1%")
      (footprint "0805_R")
      (description "贴片电阻")
      (libsource (lib "Miscellaneous Devices LC") (part "0805 1KΩ (1001) 1%"))
    )
    (comp (ref "R18")
      (value "100KΩ (1003) ±1%")
      (footprint "0402_R")
      (description "贴片电阻")
      (libsource (lib "Miscellaneous Devices LC") (part "0402 100KΩ (1003) 1%"))
    )
    (comp (ref "R19")
      (value "1KΩ (1001) ±1%")
      (footprint "0402_R")
      (description "贴片电阻")
      (libsource (lib "Miscellaneous Devices LC") (part "0402 1KΩ (1001) 1%"))
    )
    (comp (ref "R20")
      (value "15KΩ (1502) ±1%")
      (footprint "0402_R")
      (description "贴片电阻")
      (libsource (lib "Miscellaneous Devices LC") (part "0402 15KΩ (1502) 1%"))
    )
    (comp (ref "R21")
      (value "100KΩ (1003) ±1%")
      (footprint "0402_R")
      (description "贴片电阻")
      (libsource (lib "Miscellaneous Devices LC") (part "0402 100KΩ (1003) 1%"))
    )
    (comp (ref "R22")
      (value "1KΩ (1001) ±1%")
      (footprint "0402_R")
      (description "贴片电阻")
      (libsource (lib "Miscellaneous Devices LC") (part "0402 1KΩ (1001) 1%"))
    )
    (comp (ref "R23")
      (value "15KΩ (1502) ±1%")
      (footprint "0402_R")
      (description "贴片电阻")
      (libsource (lib "Miscellaneous Devices LC") (part "0402 15KΩ (1502) 1%"))
    )
    (comp (ref "R24")
      (value "100KΩ (1003) ±1%")
      (footprint "0402_R")
      (description "贴片电阻")
      (libsource (lib "Miscellaneous Devices LC") (part "0402 100KΩ (1003) 1%"))
    )
    (comp (ref "R25")
      (value "1KΩ (1001) ±1%")
      (footprint "0402_R")
      (description "贴片电阻")
      (libsource (lib "Miscellaneous Devices LC") (part "0402 1KΩ (1001) 1%"))
    )
    (comp (ref "R26")
      (value "15KΩ (1502) ±1%")
      (footprint "0402_R")
      (description "贴片电阻")
      (libsource (lib "Miscellaneous Devices LC") (part "0402 15KΩ (1502) 1%"))
    )
    (comp (ref "R27")
      (value "100KΩ (1003) ±1%")
      (footprint "0402_R")
      (description "贴片电阻")
      (libsource (lib "Miscellaneous Devices LC") (part "0402 100KΩ (1003) 1%"))
    )
    (comp (ref "R28")
      (value "1KΩ (1001) ±1%")
      (footprint "0402_R")
      (description "贴片电阻")
      (libsource (lib "Miscellaneous Devices LC") (part "0402 1KΩ (1001) 1%"))
    )
    (comp (ref "R29")
      (value "15KΩ (1502) ±1%")
      (footprint "0402_R")
      (description "贴片电阻")
      (libsource (lib "Miscellaneous Devices LC") (part "0402 15KΩ (1502) 1%"))
    )
    (comp (ref "R30")
      (value "100KΩ (1003) ±1%")
      (footprint "0402_R")
      (description "贴片电阻")
      (libsource (lib "Miscellaneous Devices LC") (part "0402 100KΩ (1003) 1%"))
    )
    (comp (ref "R31")
      (value "1KΩ (1001) ±1%")
      (footprint "0402_R")
      (description "贴片电阻")
      (libsource (lib "Miscellaneous Devices LC") (part "0402 1KΩ (1001) 1%"))
    )
    (comp (ref "R32")
      (value "15KΩ (1502) ±1%")
      (footprint "0402_R")
      (description "贴片电阻")
      (libsource (lib "Miscellaneous Devices LC") (part "0402 15KΩ (1502) 1%"))
    )
    (comp (ref "R33")
      (value "100KΩ (1003) ±1%")
      (footprint "0402_R")
      (description "贴片电阻")
      (libsource (lib "Miscellaneous Devices LC") (part "0402 100KΩ (1003) 1%"))
    )
    (comp (ref "R34")
      (value "1KΩ (1001) ±1%")
      (footprint "0402_R")
      (description "贴片电阻")
      (libsource (lib "Miscellaneous Devices LC") (part "0402 1KΩ (1001) 1%"))
    )
    (comp (ref "R35")
      (value "15KΩ (1502) ±1%")
      (footprint "0402_R")
      (description "贴片电阻")
      (libsource (lib "Miscellaneous Devices LC") (part "0402 15KΩ (1502) 1%"))
    )
    (comp (ref "R36")
      (value "100KΩ (1003) ±1%")
      (footprint "0402_R")
      (description "贴片电阻")
      (libsource (lib "Miscellaneous Devices LC") (part "0402 100KΩ (1003) 1%"))
    )
    (comp (ref "R37")
      (value "1KΩ (1001) ±1%")
      (footprint "0402_R")
      (description "贴片电阻")
      (libsource (lib "Miscellaneous Devices LC") (part "0402 1KΩ (1001) 1%"))
    )
    (comp (ref "R38")
      (value "15KΩ (1502) ±1%")
      (footprint "0402_R")
      (description "贴片电阻")
      (libsource (lib "Miscellaneous Devices LC") (part "0402 15KΩ (1502) 1%"))
    )
    (comp (ref "R39")
      (value "100KΩ (1003) ±1%")
      (footprint "0402_R")
      (description "贴片电阻")
      (libsource (lib "Miscellaneous Devices LC") (part "0402 100KΩ (1003) 1%"))
    )
    (comp (ref "R40")
      (value "1KΩ (1001) ±1%")
      (footprint "0402_R")
      (description "贴片电阻")
      (libsource (lib "Miscellaneous Devices LC") (part "0402 1KΩ (1001) 1%"))
    )
    (comp (ref "R41")
      (value "15KΩ (1502) ±1%")
      (footprint "0402_R")
      (description "贴片电阻")
      (libsource (lib "Miscellaneous Devices LC") (part "0402 15KΩ (1502) 1%"))
    )
    (comp (ref "R42")
      (value "100KΩ (1003) ±1%")
      (footprint "0402_R")
      (description "贴片电阻")
      (libsource (lib "Miscellaneous Devices LC") (part "0402 100KΩ (1003) 1%"))
    )
    (comp (ref "R43")
      (value "1KΩ (1001) ±1%")
      (footprint "0402_R")
      (description "贴片电阻")
      (libsource (lib "Miscellaneous Devices LC") (part "0402 1KΩ (1001) 1%"))
    )
    (comp (ref "R44")
      (value "15KΩ (1502) ±1%")
      (footprint "0402_R")
      (description "贴片电阻")
      (libsource (lib "Miscellaneous Devices LC") (part "0402 15KΩ (1502) 1%"))
    )
    (comp (ref "R45")
      (value "100KΩ (1003) ±1%")
      (footprint "0402_R")
      (description "贴片电阻")
      (libsource (lib "Miscellaneous Devices LC") (part "0402 100KΩ (1003) 1%"))
    )
    (comp (ref "R46")
      (value "1KΩ (1001) ±1%")
      (footprint "0402_R")
      (description "贴片电阻")
      (libsource (lib "Miscellaneous Devices LC") (part "0402 1KΩ (1001) 1%"))
    )
    (comp (ref "R47")
      (value "15KΩ (1502) ±1%")
      (footprint "0402_R")
      (description "贴片电阻")
      (libsource (lib "Miscellaneous Devices LC") (part "0402 15KΩ (1502) 1%"))
    )
    (comp (ref "R48")
      (value "100KΩ (1003) ±1%")
      (footprint "0402_R")
      (description "贴片电阻")
      (libsource (lib "Miscellaneous Devices LC") (part "0402 100KΩ (1003) 1%"))
    )
    (comp (ref "RA1")
      (value "100KΩ (1003) ±1%")
      (footprint "0402_R")
      (description "贴片电阻")
      (libsource (lib "") (part "0402 100KΩ (1003) 1%_1"))
    )
    (comp (ref "RA2")
      (value "120KΩ (1203) ±1%")
      (footprint "0402_R")
      (description "贴片电阻")
      (libsource (lib "Miscellaneous Devices LC") (part "0402 120KΩ (1203) 1%"))
    )
    (comp (ref "RA3")
      (value "3.9KΩ(3901) ±1%")
      (footprint "0402_R")
      (description "贴片电阻")
      (libsource (lib "Miscellaneous Devices LC") (part "0402 3.9KΩ(3901) 1%"))
    )
    (comp (ref "RA4")
      (value "100Ω (1000) ±1%")
      (footprint "0402_R")
      (description "贴片电阻")
      (libsource (lib "Miscellaneous Devices LC") (part "0402 100Ω (1000) 1%"))
    )
    (comp (ref "RA5")
      (value "22KΩ (2202) ±1%")
      (footprint "0402_R")
      (description "贴片电阻")
      (libsource (lib "Miscellaneous Devices LC") (part "0402 22KΩ (2202) 1%"))
    )
    (comp (ref "RA6")
      (value "1.5KΩ (1501) ±1%")
      (footprint "0402_R")
      (description "贴片电阻")
      (libsource (lib "Miscellaneous Devices LC") (part "0402 1.5KΩ (1501) 1%"))
    )
    (comp (ref "RA7")
      (value "200Ω (2000) ±1%")
      (footprint "0402_R")
      (description "贴片电阻")
      (libsource (lib "Miscellaneous Devices LC") (part "0402 200Ω (2000) 1%"))
    )
    (comp (ref "RA8")
      (value "0Ω (0R0) ±1%")
      (footprint "0805_R")
      (description "贴片电阻")
      (libsource (lib "Miscellaneous Devices LC") (part "0805 0Ω (0R0) 1%"))
    )
    (comp (ref "RB1")
      (value "100KΩ (1003) ±1%")
      (footprint "0402_R")
      (description "贴片电阻")
      (libsource (lib "") (part "0402 100KΩ (1003) 1%_1"))
    )
    (comp (ref "RB2")
      (value "120KΩ (1203) ±1%")
      (footprint "0402_R")
      (description "贴片电阻")
      (libsource (lib "Miscellaneous Devices LC") (part "0402 120KΩ (1203) 1%"))
    )
    (comp (ref "RB3")
      (value "3.9KΩ(3901) ±1%")
      (footprint "0402_R")
      (description "贴片电阻")
      (libsource (lib "Miscellaneous Devices LC") (part "0402 3.9KΩ(3901) 1%"))
    )
    (comp (ref "RB4")
      (value "100Ω (1000) ±1%")
      (footprint "0402_R")
      (description "贴片电阻")
      (libsource (lib "Miscellaneous Devices LC") (part "0402 100Ω (1000) 1%"))
    )
    (comp (ref "RB5")
      (value "5.1KΩ (5101) ±1%")
      (footprint "0402_R")
      (description "贴片电阻")
      (libsource (lib "Miscellaneous Devices LC") (part "0402 5.1KΩ (5101) 1%"))
    )
    (comp (ref "RB6")
      (value "3.3KΩ (3301) ±1%")
      (footprint "0402_R")
      (description "贴片电阻")
      (libsource (lib "Miscellaneous Devices LC") (part "0402 3.3KΩ (3301) 1%"))
    )
    (comp (ref "RB7")
      (value "470Ω (4700) ±1%")
      (footprint "0402_R")
      (description "贴片电阻")
      (libsource (lib "Miscellaneous Devices LC") (part "0402 470Ω (4700) 1%"))
    )
    (comp (ref "RB8")
      (value "0Ω (0R0) ±1%")
      (footprint "0805_R")
      (description "贴片电阻")
      (libsource (lib "Miscellaneous Devices LC") (part "0805 0Ω (0R0) 1%"))
    )
    (comp (ref "RI1")
      (value "10KΩ (1002) ±1%")
      (footprint "0402_R")
      (description "贴片电阻")
      (fields (field (name "VAL") "10K"))
      (libsource (lib "") (part "0402 10KΩ (1002) 1%_1"))
    )
    (comp (ref "RI2")
      (value "10KΩ (1002) ±1%")
      (footprint "0402_R")
      (description "贴片电阻")
      (fields (field (name "VAL") "10K"))
      (libsource (lib "LJ_Mosfet_Power") (part "0402 10KΩ (1002) 1%"))
    )
    (comp (ref "RI3")
      (value "10KΩ (1002) ±1%")
      (footprint "0402_R")
      (description "贴片电阻")
      (fields (field (name "VAL") "10K"))
      (libsource (lib "LJ_Mosfet_Power") (part "0402 10KΩ (1002) 1%"))
    )
    (comp (ref "RI4")
      (value "10KΩ (1002) ±1%")
      (footprint "0402_R")
      (description "贴片电阻")
      (fields (field (name "VAL") "10K"))
      (libsource (lib "") (part "0402 10KΩ (1002) 1%_1"))
    )
    (comp (ref "RI5")
      (value "10KΩ (1002) ±1%")
      (footprint "0402_R")
      (description "贴片电阻")
      (fields (field (name "VAL") "10K"))
      (libsource (lib "") (part "0402 10KΩ (1002) 1%_1"))
    )
    (comp (ref "RI6")
      (value "0Ω (0R0) ±1%")
      (footprint "0402_R")
      (description "贴片电阻")
      (libsource (lib "Miscellaneous Devices LC") (part "0402 0Ω (0R0) 1%"))
    )
    (comp (ref "RI7")
      (value "0Ω (0R0) ±1%")
      (footprint "0402_R")
      (description "贴片电阻")
      (libsource (lib "Miscellaneous Devices LC") (part "0402 0Ω (0R0) 1%"))
    )
    (comp (ref "RI8")
      (value "0Ω (0R0) ±1%")
      (footprint "0402_R")
      (description "贴片电阻")
      (libsource (lib "Miscellaneous Devices LC") (part "0402 0Ω (0R0) 1%"))
    )
    (comp (ref "RI9")
      (value "0Ω (0R0) ±1%")
      (footprint "0402_R")
      (description "贴片电阻")
      (libsource (lib "Miscellaneous Devices LC") (part "0402 0Ω (0R0) 1%"))
    )
    (comp (ref "RL_01")
      (value "20KΩ (2002) ±1%")
      (footprint "0603_R")
      (description "贴片电阻")
      (libsource (lib "Miscellaneous Devices LC") (part "0603 20KΩ (2002) 1%"))
    )
    (comp (ref "RL_02")
      (value "20KΩ (2002) ±1%")
      (footprint "0603_R")
      (description "贴片电阻")
      (libsource (lib "Miscellaneous Devices LC") (part "0603 20KΩ (2002) 1%"))
    )
    (comp (ref "RL_03")
      (value "20KΩ (2002) ±1%")
      (footprint "0603_R")
      (description "贴片电阻")
      (libsource (lib "Miscellaneous Devices LC") (part "0603 20KΩ (2002) 1%"))
    )
    (comp (ref "RL_04")
      (value "20KΩ (2002) ±1%")
      (footprint "0603_R")
      (description "贴片电阻")
      (libsource (lib "Miscellaneous Devices LC") (part "0603 20KΩ (2002) 1%"))
    )
    (comp (ref "RL_05")
      (value "20KΩ (2002) ±1%")
      (footprint "0603_R")
      (description "贴片电阻")
      (libsource (lib "Miscellaneous Devices LC") (part "0603 20KΩ (2002) 1%"))
    )
    (comp (ref "RL_06")
      (value "20KΩ (2002) ±1%")
      (footprint "0603_R")
      (description "贴片电阻")
      (libsource (lib "Miscellaneous Devices LC") (part "0603 20KΩ (2002) 1%"))
    )
    (comp (ref "RL_07")
      (value "20KΩ (2002) ±1%")
      (footprint "0603_R")
      (description "贴片电阻")
      (libsource (lib "Miscellaneous Devices LC") (part "0603 20KΩ (2002) 1%"))
    )
    (comp (ref "RL_08")
      (value "20KΩ (2002) ±1%")
      (footprint "0603_R")
      (description "贴片电阻")
      (libsource (lib "Miscellaneous Devices LC") (part "0603 20KΩ (2002) 1%"))
    )
    (comp (ref "RL_09")
      (value "20KΩ (2002) ±1%")
      (footprint "0603_R")
      (description "贴片电阻")
      (libsource (lib "Miscellaneous Devices LC") (part "0603 20KΩ (2002) 1%"))
    )
    (comp (ref "RL_10")
      (value "20KΩ (2002) ±1%")
      (footprint "0603_R")
      (description "贴片电阻")
      (libsource (lib "Miscellaneous Devices LC") (part "0603 20KΩ (2002) 1%"))
    )
    (comp (ref "RL_11")
      (value "20KΩ (2002) ±1%")
      (footprint "0603_R")
      (description "贴片电阻")
      (libsource (lib "Miscellaneous Devices LC") (part "0603 20KΩ (2002) 1%"))
    )
    (comp (ref "RL_12")
      (value "20KΩ (2002) ±1%")
      (footprint "0603_R")
      (description "贴片电阻")
      (libsource (lib "Miscellaneous Devices LC") (part "0603 20KΩ (2002) 1%"))
    )
    (comp (ref "RL_13")
      (value "20KΩ (2002) ±1%")
      (footprint "0603_R")
      (description "贴片电阻")
      (libsource (lib "Miscellaneous Devices LC") (part "0603 20KΩ (2002) 1%"))
    )
    (comp (ref "RL_14")
      (value "20KΩ (2002) ±1%")
      (footprint "0603_R")
      (description "贴片电阻")
      (libsource (lib "Miscellaneous Devices LC") (part "0603 20KΩ (2002) 1%"))
    )
    (comp (ref "RL_15")
      (value "20KΩ (2002) ±1%")
      (footprint "0603_R")
      (description "贴片电阻")
      (libsource (lib "Miscellaneous Devices LC") (part "0603 20KΩ (2002) 1%"))
    )
    (comp (ref "RL_16")
      (value "20KΩ (2002) ±1%")
      (footprint "0603_R")
      (description "贴片电阻")
      (libsource (lib "Miscellaneous Devices LC") (part "0603 20KΩ (2002) 1%"))
    )
    (comp (ref "RL_17")
      (value "20KΩ (2002) ±1%")
      (footprint "0603_R")
      (description "贴片电阻")
      (libsource (lib "Miscellaneous Devices LC") (part "0603 20KΩ (2002) 1%"))
    )
    (comp (ref "RL_18")
      (value "20KΩ (2002) ±1%")
      (footprint "0603_R")
      (description "贴片电阻")
      (libsource (lib "Miscellaneous Devices LC") (part "0603 20KΩ (2002) 1%"))
    )
    (comp (ref "RL_19")
      (value "20KΩ (2002) ±1%")
      (footprint "0603_R")
      (description "贴片电阻")
      (libsource (lib "Miscellaneous Devices LC") (part "0603 20KΩ (2002) 1%"))
    )
    (comp (ref "RL_20")
      (value "20KΩ (2002) ±1%")
      (footprint "0603_R")
      (description "贴片电阻")
      (libsource (lib "Miscellaneous Devices LC") (part "0603 20KΩ (2002) 1%"))
    )
    (comp (ref "RP1-4")
      (value "10KΩ (103) ±5%")
      (footprint "0603_Rx4")
      (description "贴片排阻")
      (libsource (lib "Miscellaneous Devices LC") (part "0603*4  10KΩ (103) 5%"))
    )
    (comp (ref "RP5-8")
      (value "10KΩ (103) ±5%")
      (footprint "0603_Rx4")
      (description "贴片排阻")
      (libsource (lib "Miscellaneous Devices LC") (part "0603*4  10KΩ (103) 5%"))
    )
    (comp (ref "RP9-12")
      (value "10KΩ (103) ±5%")
      (footprint "0603_Rx4")
      (description "贴片排阻")
      (libsource (lib "Miscellaneous Devices LC") (part "0603*4  10KΩ (103) 5%"))
    )
    (comp (ref "RP13-16")
      (value "10KΩ (103) ±5%")
      (footprint "0603_Rx4")
      (description "贴片排阻")
      (libsource (lib "Miscellaneous Devices LC") (part "0603*4  10KΩ (103) 5%"))
    )
    (comp (ref "RP17-20")
      (value "10KΩ (103) ±5%")
      (footprint "0603_Rx4")
      (description "贴片排阻")
      (libsource (lib "Miscellaneous Devices LC") (part "0603*4  10KΩ (103) 5%"))
    )
    (comp (ref "RQ1")
      (value "0.01Ω(R010) ±1% 1W")
      (footprint "R2512")
      (description "贴片合金电阻")
      (libsource (lib "Active_crystal") (part "R"))
    )
    (comp (ref "RQ2")
      (value "0.01Ω(R010) ±1% 1W")
      (footprint "R2512")
      (description "贴片合金电阻")
      (libsource (lib "Active_crystal") (part "R"))
    )
    (comp (ref "RQ3")
      (value "0.01Ω(R010) ±1% 1W")
      (footprint "R2512")
      (description "贴片合金电阻")
      (libsource (lib "Active_crystal") (part "R"))
    )
    (comp (ref "RQ4")
      (value "0.01Ω(R010) ±1% 1W")
      (footprint "R2512")
      (description "贴片合金电阻")
      (libsource (lib "Active_crystal") (part "R"))
    )
    (comp (ref "RQ5")
      (value "0.01Ω(R010) ±1% 1W")
      (footprint "R2512")
      (description "贴片合金电阻")
      (libsource (lib "Active_crystal") (part "R"))
    )
    (comp (ref "RQ6")
      (value "0.01Ω(R010) ±1% 1W")
      (footprint "R2512")
      (description "贴片合金电阻")
      (libsource (lib "Active_crystal") (part "R"))
    )
    (comp (ref "RQ7")
      (value "0.01Ω(R010) ±1% 1W")
      (footprint "R2512")
      (description "贴片合金电阻")
      (libsource (lib "Active_crystal") (part "R"))
    )
    (comp (ref "RQ8")
      (value "0.01Ω(R010) ±1% 1W")
      (footprint "R2512")
      (description "贴片合金电阻")
      (libsource (lib "Active_crystal") (part "R"))
    )
    (comp (ref "RQ9")
      (value "0.01Ω(R010) ±1% 1W")
      (footprint "R2512")
      (description "贴片合金电阻")
      (libsource (lib "Active_crystal") (part "R"))
    )
    (comp (ref "RQ10")
      (value "0.01Ω(R010) ±1% 1W")
      (footprint "R2512")
      (description "贴片合金电阻")
      (libsource (lib "Active_crystal") (part "R"))
    )
    (comp (ref "RQ11")
      (value "0.01Ω(R010) ±1% 1W")
      (footprint "R2512")
      (description "贴片合金电阻")
      (libsource (lib "Active_crystal") (part "R"))
    )
    (comp (ref "RQ12")
      (value "0.01Ω(R010) ±1% 1W")
      (footprint "R2512")
      (description "贴片合金电阻")
      (libsource (lib "Active_crystal") (part "R"))
    )
    (comp (ref "RQ13")
      (value "0.01Ω(R010) ±1% 1W")
      (footprint "R2512")
      (description "贴片合金电阻")
      (libsource (lib "Active_crystal") (part "R"))
    )
    (comp (ref "RQ14")
      (value "0.01Ω(R010) ±1% 1W")
      (footprint "R2512")
      (description "贴片合金电阻")
      (libsource (lib "Active_crystal") (part "R"))
    )
    (comp (ref "RQ15")
      (value "0.01Ω(R010) ±1% 1W")
      (footprint "R2512")
      (description "贴片合金电阻")
      (libsource (lib "Active_crystal") (part "R"))
    )
    (comp (ref "RQ16")
      (value "0.01Ω(R010) ±1% 1W")
      (footprint "R2512")
      (description "贴片合金电阻")
      (libsource (lib "Active_crystal") (part "R"))
    )
    (comp (ref "RQ17")
      (value "0.01Ω(R010) ±1% 1W")
      (footprint "R2512")
      (description "贴片合金电阻")
      (libsource (lib "Active_crystal") (part "R"))
    )
    (comp (ref "RQ18")
      (value "0.01Ω(R010) ±1% 1W")
      (footprint "R2512")
      (description "贴片合金电阻")
      (libsource (lib "Active_crystal") (part "R"))
    )
    (comp (ref "R_J5V")
      (value "0Ω (0R0) ±1%")
      (footprint "0805_R")
      (description "贴片电阻")
      (libsource (lib "Miscellaneous Devices LC") (part "0805 0Ω (0R0) 1%"))
    )
    (comp (ref "SA1")
      (value "CMS01")
      (footprint "M-FLAT")
      (description "TVS")
      (libsource (lib "LJ_Mosfet_Power") (part "D Zener"))
    )
    (comp (ref "SB1")
      (value "CMS01")
      (footprint "M-FLAT")
      (description "TVS")
      (libsource (lib "LJ_Mosfet_Power") (part "D Zener"))
    )
    (comp (ref "TVS")
      (value "US1M")
      (footprint "SMA(DO-214AC)_S1")
      (description "二极管")
      (libsource (lib "Miscellaneous Devices LC") (part "SMA(DO-214AC) US1M"))
    )
    (comp (ref "U-05")
      (value "BL9342")
      (footprint "SOT23-6")
      (description "40V, 600mA , Step-Down Converter,DC-DC芯片")
      (libsource (lib "LJ_Mosfet_Power") (part "BL9342"))
    )
    (comp (ref "U-12")
      (value "BL9342")
      (footprint "SOT23-6")
      (description "40V, 600mA , Step-Down Converter,DC-DC芯片")
      (libsource (lib "LJ_Mosfet_Power") (part "BL9342"))
    )
    (comp (ref "U1-2")
      (value "LTC1255CS8")
      (footprint "LC-SOIC-8_150mil")
      (description "24V双路高侧NMOS驱动IC")
      (libsource (lib "Active_crystal") (part "LTC1255"))
    )
    (comp (ref "U3-4")
      (value "LTC1255CS8")
      (footprint "LC-SOIC-8_150mil")
      (libsource (lib "Active_crystal") (part "LTC1255"))
    )
    (comp (ref "U5-6")
      (value "LTC1255CS8")
      (footprint "LC-SOIC-8_150mil")
      (libsource (lib "Active_crystal") (part "LTC1255"))
    )
    (comp (ref "U7-8")
      (value "LTC1255CS8")
      (footprint "LC-SOIC-8_150mil")
      (libsource (lib "Active_crystal") (part "LTC1255"))
    )
    (comp (ref "U9-10")
      (value "LTC1255CS8")
      (footprint "LC-SOIC-8_150mil")
      (libsource (lib "Active_crystal") (part "LTC1255"))
    )
    (comp (ref "U11-12")
      (value "LTC1255CS8")
      (footprint "LC-SOIC-8_150mil")
      (libsource (lib "Active_crystal") (part "LTC1255"))
    )
    (comp (ref "U13-14")
      (value "LTC1255CS8")
      (footprint "LC-SOIC-8_150mil")
      (libsource (lib "Active_crystal") (part "LTC1255"))
    )
    (comp (ref "U15-16")
      (value "LTC1255CS8")
      (footprint "LC-SOIC-8_150mil")
      (libsource (lib "Active_crystal") (part "LTC1255"))
    )
    (comp (ref "U17-18")
      (value "LTC1255CS8")
      (footprint "LC-SOIC-8_150mil")
      (libsource (lib "Active_crystal") (part "LTC1255"))
    )
    (comp (ref "U24") (value "TC4427") (footprint "SOIC8") (libsource (lib "Active_crystal") (part "TC4427")))
    (comp (ref "UIO")
      (value "MCP23017-E/SO")
      (footprint "SSOP28")
      (description "16-Bit I/O Expander with Serial Interface")
      (libsource (lib "LJ_Mosfet_Power") (part "MCP23017-E/SO"))
    )
    (comp (ref "ZD1")
      (value "LBZT52C12T1G")
      (footprint "SOD123")
      (description "Surface Mount Zener Diodes")
      (libsource (lib "Active_crystal") (part "Zener Diode"))
    )
    (comp (ref "ZD2")
      (value "LBZT52C12T1G")
      (footprint "SOD123")
      (description "Surface Mount Zener Diodes")
      (libsource (lib "Active_crystal") (part "Zener Diode"))
    )
    (comp (ref "ZD3")
      (value "LBZT52C12T1G")
      (footprint "SOD123")
      (description "Surface Mount Zener Diodes")
      (libsource (lib "Active_crystal") (part "Zener Diode"))
    )
    (comp (ref "ZD4")
      (value "LBZT52C12T1G")
      (footprint "SOD123")
      (description "Surface Mount Zener Diodes")
      (libsource (lib "Active_crystal") (part "Zener Diode"))
    )
    (comp (ref "ZD5")
      (value "LBZT52C12T1G")
      (footprint "SOD123")
      (description "Surface Mount Zener Diodes")
      (libsource (lib "Active_crystal") (part "Zener Diode"))
    )
    (comp (ref "ZD6")
      (value "LBZT52C12T1G")
      (footprint "SOD123")
      (description "Surface Mount Zener Diodes")
      (libsource (lib "Active_crystal") (part "Zener Diode"))
    )
    (comp (ref "ZD7")
      (value "LBZT52C12T1G")
      (footprint "SOD123")
      (description "Surface Mount Zener Diodes")
      (libsource (lib "Active_crystal") (part "Zener Diode"))
    )
    (comp (ref "ZD8")
      (value "LBZT52C12T1G")
      (footprint "SOD123")
      (description "Surface Mount Zener Diodes")
      (libsource (lib "Active_crystal") (part "Zener Diode"))
    )
    (comp (ref "ZD9")
      (value "LBZT52C12T1G")
      (footprint "SOD123")
      (description "Surface Mount Zener Diodes")
      (libsource (lib "Active_crystal") (part "Zener Diode"))
    )
    (comp (ref "ZD10")
      (value "LBZT52C12T1G")
      (footprint "SOD123")
      (description "Surface Mount Zener Diodes")
      (libsource (lib "Active_crystal") (part "Zener Diode"))
    )
    (comp (ref "ZD11")
      (value "LBZT52C12T1G")
      (footprint "SOD123")
      (description "Surface Mount Zener Diodes")
      (libsource (lib "Active_crystal") (part "Zener Diode"))
    )
    (comp (ref "ZD12")
      (value "LBZT52C12T1G")
      (footprint "SOD123")
      (description "Surface Mount Zener Diodes")
      (libsource (lib "Active_crystal") (part "Zener Diode"))
    )
    (comp (ref "ZD13")
      (value "LBZT52C12T1G")
      (footprint "SOD123")
      (description "Surface Mount Zener Diodes")
      (libsource (lib "Active_crystal") (part "Zener Diode"))
    )
    (comp (ref "ZD14")
      (value "LBZT52C12T1G")
      (footprint "SOD123")
      (description "Surface Mount Zener Diodes")
      (libsource (lib "Active_crystal") (part "Zener Diode"))
    )
    (comp (ref "ZD15")
      (value "LBZT52C12T1G")
      (footprint "SOD123")
      (description "Surface Mount Zener Diodes")
      (libsource (lib "Active_crystal") (part "Zener Diode"))
    )
    (comp (ref "ZD16")
      (value "LBZT52C12T1G")
      (footprint "SOD123")
      (description "Surface Mount Zener Diodes")
      (libsource (lib "Active_crystal") (part "Zener Diode"))
    )
    (comp (ref "ZD17")
      (value "LBZT52C12T1G")
      (footprint "SOD123")
      (description "Surface Mount Zener Diodes")
      (libsource (lib "Active_crystal") (part "Zener Diode"))
    )
    (comp (ref "ZD18")
      (value "LBZT52C12T1G")
      (footprint "SOD123")
      (description "Surface Mount Zener Diodes")
      (libsource (lib "Active_crystal") (part "Zener Diode"))
    )
    (comp (ref "ZD19")
      (value "LBZT52C12T1G")
      (footprint "SOD123")
      (description "Surface Mount Zener Diodes")
      (libsource (lib "Active_crystal") (part "Zener Diode"))
    )
    (comp (ref "ZD20")
      (value "LBZT52C12T1G")
      (footprint "SOD123")
      (description "Surface Mount Zener Diodes")
      (libsource (lib "Active_crystal") (part "Zener Diode"))
    )
    (comp (ref "ZM01")
      (value "ZMM3V3")
      (footprint "LL-34")
      (description "稳压二极管")
      (libsource (lib "Miscellaneous Devices LC") (part "LL-34 ZMM3V3"))
    )
    (comp (ref "ZM02")
      (value "ZMM3V3")
      (footprint "LL-34")
      (description "稳压二极管")
      (libsource (lib "Miscellaneous Devices LC") (part "LL-34 ZMM3V3"))
    )
    (comp (ref "ZM03")
      (value "ZMM3V3")
      (footprint "LL-34")
      (description "稳压二极管")
      (libsource (lib "Miscellaneous Devices LC") (part "LL-34 ZMM3V3"))
    )
    (comp (ref "ZM04")
      (value "ZMM3V3")
      (footprint "LL-34")
      (description "稳压二极管")
      (libsource (lib "Miscellaneous Devices LC") (part "LL-34 ZMM3V3"))
    )
    (comp (ref "ZM05")
      (value "ZMM3V3")
      (footprint "LL-34")
      (description "稳压二极管")
      (libsource (lib "Miscellaneous Devices LC") (part "LL-34 ZMM3V3"))
    )
    (comp (ref "ZM06")
      (value "ZMM3V3")
      (footprint "LL-34")
      (description "稳压二极管")
      (libsource (lib "Miscellaneous Devices LC") (part "LL-34 ZMM3V3"))
    )
    (comp (ref "ZM07")
      (value "ZMM3V3")
      (footprint "LL-34")
      (description "稳压二极管")
      (libsource (lib "Miscellaneous Devices LC") (part "LL-34 ZMM3V3"))
    )
    (comp (ref "ZM08")
      (value "ZMM3V3")
      (footprint "LL-34")
      (description "稳压二极管")
      (libsource (lib "Miscellaneous Devices LC") (part "LL-34 ZMM3V3"))
    )
    (comp (ref "ZM09")
      (value "ZMM3V3")
      (footprint "LL-34")
      (description "稳压二极管")
      (libsource (lib "Miscellaneous Devices LC") (part "LL-34 ZMM3V3"))
    )
    (comp (ref "ZM10")
      (value "ZMM3V3")
      (footprint "LL-34")
      (description "稳压二极管")
      (libsource (lib "Miscellaneous Devices LC") (part "LL-34 ZMM3V3"))
    )
    (comp (ref "ZM11")
      (value "ZMM3V3")
      (footprint "LL-34")
      (description "稳压二极管")
      (libsource (lib "Miscellaneous Devices LC") (part "LL-34 ZMM3V3"))
    )
    (comp (ref "ZM12")
      (value "ZMM3V3")
      (footprint "LL-34")
      (description "稳压二极管")
      (libsource (lib "Miscellaneous Devices LC") (part "LL-34 ZMM3V3"))
    )
    (comp (ref "ZM13")
      (value "ZMM3V3")
      (footprint "LL-34")
      (description "稳压二极管")
      (libsource (lib "Miscellaneous Devices LC") (part "LL-34 ZMM3V3"))
    )
    (comp (ref "ZM14")
      (value "ZMM3V3")
      (footprint "LL-34")
      (description "稳压二极管")
      (libsource (lib "Miscellaneous Devices LC") (part "LL-34 ZMM3V3"))
    )
    (comp (ref "ZM15")
      (value "ZMM3V3")
      (footprint "LL-34")
      (description "稳压二极管")
      (libsource (lib "Miscellaneous Devices LC") (part "LL-34 ZMM3V3"))
    )
    (comp (ref "ZM16")
      (value "ZMM3V3")
      (footprint "LL-34")
      (description "稳压二极管")
      (libsource (lib "Miscellaneous Devices LC") (part "LL-34 ZMM3V3"))
    )
  )
  (nets
    (net (code "1") (name "/INTA") (class "Default")
      (node (ref "JR") (pin "21") (pinfunction "21_21") (pintype "passive"))
      (node (ref "RI6") (pin "2") (pinfunction "2_2") (pintype "passive"))
    )
    (net (code "2") (name "/INTB") (class "Default")
      (node (ref "JR") (pin "22") (pinfunction "22_22") (pintype "passive"))
      (node (ref "RI7") (pin "2") (pinfunction "2_2") (pintype "passive"))
    )
    (net (code "3") (name "/K_Ctrl_01") (class "Default")
      (node (ref "JR") (pin "20") (pinfunction "20_20") (pintype "passive"))
      (node (ref "RP1-4") (pin "4") (pinfunction "4_4") (pintype "passive"))
      (node (ref "U1-2") (pin "4") (pinfunction "IN1_4") (pintype "passive"))
    )
    (net (code "4") (name "/K_Ctrl_02") (class "Default")
      (node (ref "JR") (pin "19") (pinfunction "19_19") (pintype "passive"))
      (node (ref "RP1-4") (pin "3") (pinfunction "3_3") (pintype "passive"))
      (node (ref "U1-2") (pin "5") (pinfunction "IN2_5") (pintype "passive"))
    )
    (net (code "5") (name "/K_Ctrl_03") (class "Default")
      (node (ref "JR") (pin "18") (pinfunction "18_18") (pintype "passive"))
      (node (ref "RP1-4") (pin "2") (pinfunction "2_2") (pintype "passive"))
      (node (ref "U3-4") (pin "4") (pinfunction "IN1_4") (pintype "passive"))
    )
    (net (code "6") (name "/K_Ctrl_04") (class "Default")
      (node (ref "JR") (pin "17") (pinfunction "17_17") (pintype "passive"))
      (node (ref "RP1-4") (pin "1") (pinfunction "1_1") (pintype "passive"))
      (node (ref "U3-4") (pin "5") (pinfunction "IN2_5") (pintype "passive"))
    )
    (net (code "7") (name "/K_Ctrl_05") (class "Default")
      (node (ref "JR") (pin "16") (pinfunction "16_16") (pintype "passive"))
      (node (ref "RP5-8") (pin "4") (pinfunction "4_4") (pintype "passive"))
      (node (ref "U5-6") (pin "4") (pinfunction "IN1_4") (pintype "passive"))
    )
    (net (code "8") (name "/K_Ctrl_06") (class "Default")
      (node (ref "JR") (pin "15") (pinfunction "15_15") (pintype "passive"))
      (node (ref "RP5-8") (pin "3") (pinfunction "3_3") (pintype "passive"))
      (node (ref "U5-6") (pin "5") (pinfunction "IN2_5") (pintype "passive"))
    )
    (net (code "9") (name "/K_Ctrl_07") (class "Default")
      (node (ref "JR") (pin "14") (pinfunction "14_14") (pintype "passive"))
      (node (ref "RP5-8") (pin "2") (pinfunction "2_2") (pintype "passive"))
      (node (ref "U7-8") (pin "4") (pinfunction "IN1_4") (pintype "passive"))
    )
    (net (code "10") (name "/K_Ctrl_08") (class "Default")
      (node (ref "JR") (pin "13") (pinfunction "13_13") (pintype "passive"))
      (node (ref "RP5-8") (pin "1") (pinfunction "1_1") (pintype "passive"))
      (node (ref "U7-8") (pin "5") (pinfunction "IN2_5") (pintype "passive"))
    )
    (net (code "11") (name "/K_Ctrl_09") (class "Default")
      (node (ref "JR") (pin "12") (pinfunction "12_12") (pintype "passive"))
      (node (ref "RP9-12") (pin "4") (pinfunction "4_4") (pintype "passive"))
      (node (ref "U9-10") (pin "4") (pinfunction "IN1_4") (pintype "passive"))
    )
    (net (code "12") (name "/K_Ctrl_10") (class "Default")
      (node (ref "JR") (pin "11") (pinfunction "11_11") (pintype "passive"))
      (node (ref "RP9-12") (pin "3") (pinfunction "3_3") (pintype "passive"))
      (node (ref "U9-10") (pin "5") (pinfunction "IN2_5") (pintype "passive"))
    )
    (net (code "13") (name "/K_Ctrl_11") (class "Default")
      (node (ref "JR") (pin "10") (pinfunction "10_10") (pintype "passive"))
      (node (ref "RP9-12") (pin "2") (pinfunction "2_2") (pintype "passive"))
      (node (ref "U11-12") (pin "4") (pinfunction "IN1_4") (pintype "passive"))
    )
    (net (code "14") (name "/K_Ctrl_12") (class "Default")
      (node (ref "JR") (pin "9") (pinfunction "9_9") (pintype "passive"))
      (node (ref "RP9-12") (pin "1") (pinfunction "1_1") (pintype "passive"))
      (node (ref "U11-12") (pin "5") (pinfunction "IN2_5") (pintype "passive"))
    )
    (net (code "15") (name "/K_Ctrl_13") (class "Default")
      (node (ref "JR") (pin "8") (pinfunction "8_8") (pintype "passive"))
      (node (ref "RP13-16") (pin "4") (pinfunction "4_4") (pintype "passive"))
      (node (ref "U13-14") (pin "4") (pinfunction "IN1_4") (pintype "passive"))
    )
    (net (code "16") (name "/K_Ctrl_14") (class "Default")
      (node (ref "JR") (pin "7") (pinfunction "7_7") (pintype "passive"))
      (node (ref "RP13-16") (pin "3") (pinfunction "3_3") (pintype "passive"))
      (node (ref "U13-14") (pin "5") (pinfunction "IN2_5") (pintype "passive"))
    )
    (net (code "17") (name "/K_Ctrl_15") (class "Default")
      (node (ref "JR") (pin "6") (pinfunction "6_6") (pintype "passive"))
      (node (ref "RP13-16") (pin "2") (pinfunction "2_2") (pintype "passive"))
      (node (ref "U15-16") (pin "4") (pinfunction "IN1_4") (pintype "passive"))
    )
    (net (code "18") (name "/K_Ctrl_16") (class "Default")
      (node (ref "JR") (pin "5") (pinfunction "5_5") (pintype "passive"))
      (node (ref "RP13-16") (pin "1") (pinfunction "1_1") (pintype "passive"))
      (node (ref "U15-16") (pin "5") (pinfunction "IN2_5") (pintype "passive"))
    )
    (net (code "19") (name "/K_Ctrl_17") (class "Default")
      (node (ref "JR") (pin "4") (pinfunction "4_4") (pintype "passive"))
      (node (ref "RP17-20") (pin "4") (pinfunction "4_4") (pintype "passive"))
      (node (ref "U17-18") (pin "4") (pinfunction "IN1_4") (pintype "passive"))
    )
    (net (code "20") (name "/K_Ctrl_18") (class "Default")
      (node (ref "JR") (pin "3") (pinfunction "3_3") (pintype "passive"))
      (node (ref "RP17-20") (pin "3") (pinfunction "3_3") (pintype "passive"))
      (node (ref "U17-18") (pin "5") (pinfunction "IN2_5") (pintype "passive"))
    )
    (net (code "21") (name "/K_Ctrl_19") (class "Default")
      (node (ref "JR") (pin "2") (pinfunction "2_2") (pintype "passive"))
      (node (ref "RP17-20") (pin "2") (pinfunction "2_2") (pintype "passive"))
      (node (ref "U24") (pin "2") (pinfunction "IN_A_2") (pintype "passive"))
    )
    (net (code "22") (name "/K_Ctrl_20") (class "Default")
      (node (ref "JR") (pin "1") (pinfunction "1_1") (pintype "passive"))
      (node (ref "RP17-20") (pin "1") (pinfunction "1_1") (pintype "passive"))
      (node (ref "U24") (pin "4") (pinfunction "IN_B_4") (pintype "passive"))
    )
    (net (code "23") (name "/K_Out_01") (class "Default")
      (node (ref "DP1") (pin "2") (pinfunction "K_2") (pintype "passive"))
      (node (ref "DX_1") (pin "2") (pintype "passive"))
      (node (ref "P_OUT") (pin "3") (pinfunction "3_3") (pintype "passive"))
      (node (ref "R3") (pin "2") (pinfunction "2_2") (pintype "passive"))
      (node (ref "RL_01") (pin "2") (pinfunction "2_2") (pintype "passive"))
    )
    (net (code "24") (name "/K_Out_02") (class "Default")
      (node (ref "DP2") (pin "2") (pinfunction "K_2") (pintype "passive"))
      (node (ref "DX_2") (pin "2") (pintype "passive"))
      (node (ref "P_OUT") (pin "2") (pinfunction "2_2") (pintype "passive"))
      (node (ref "R6") (pin "2") (pinfunction "2_2") (pintype "passive"))
      (node (ref "RL_02") (pin "2") (pinfunction "2_2") (pintype "passive"))
    )
    (net (code "25") (name "/K_Out_03") (class "Default")
      (node (ref "DP3") (pin "2") (pinfunction "K_2") (pintype "passive"))
      (node (ref "DX_3") (pin "2") (pintype "passive"))
      (node (ref "P_OUT") (pin "1") (pinfunction "1_1") (pintype "passive"))
      (node (ref "R9") (pin "2") (pinfunction "2_2") (pintype "passive"))
      (node (ref "RL_03") (pin "2") (pinfunction "2_2") (pintype "passive"))
    )
    (net (code "26") (name "/K_Out_04") (class "Default")
      (node (ref "DP4") (pin "2") (pinfunction "K_2") (pintype "passive"))
      (node (ref "DX_4") (pin "2") (pintype "passive"))
      (node (ref "P_OUT") (pin "13") (pinfunction "13_13") (pintype "passive"))
      (node (ref "R12") (pin "2") (pinfunction "2_2") (pintype "passive"))
      (node (ref "RL_04") (pin "2") (pinfunction "2_2") (pintype "passive"))
    )
    (net (code "27") (name "/K_Out_05") (class "Default")
      (node (ref "DP5") (pin "2") (pinfunction "K_2") (pintype "passive"))
      (node (ref "DX_5") (pin "2") (pintype "passive"))
      (node (ref "P_OUT") (pin "14") (pinfunction "14_14") (pintype "passive"))
      (node (ref "R15") (pin "2") (pinfunction "2_2") (pintype "passive"))
      (node (ref "RL_05") (pin "2") (pinfunction "2_2") (pintype "passive"))
    )
    (net (code "28") (name "/K_Out_06") (class "Default")
      (node (ref "DP6") (pin "2") (pinfunction "K_2") (pintype "passive"))
      (node (ref "DX_6") (pin "2") (pintype "passive"))
      (node (ref "P_OUT") (pin "15") (pinfunction "15_15") (pintype "passive"))
      (node (ref "R18") (pin "2") (pinfunction "2_2") (pintype "passive"))
      (node (ref "RL_06") (pin "2") (pinfunction "2_2") (pintype "passive"))
    )
    (net (code "29") (name "/K_Out_07") (class "Default")
      (node (ref "DP7") (pin "2") (pinfunction "K_2") (pintype "passive"))
      (node (ref "DX_7") (pin "2") (pintype "passive"))
      (node (ref "P_OUT") (pin "16") (pinfunction "16_16") (pintype "passive"))
      (node (ref "R21") (pin "2") (pinfunction "2_2") (pintype "passive"))
      (node (ref "RL_07") (pin "2") (pinfunction "2_2") (pintype "passive"))
    )
    (net (code "30") (name "/K_Out_08") (class "Default")
      (node (ref "DP8") (pin "2") (pinfunction "K_2") (pintype "passive"))
      (node (ref "DX_8") (pin "2") (pintype "passive"))
      (node (ref "P_OUT") (pin "17") (pinfunction "17_17") (pintype "passive"))
      (node (ref "R24") (pin "2") (pinfunction "2_2") (pintype "passive"))
      (node (ref "RL_08") (pin "2") (pinfunction "2_2") (pintype "passive"))
    )
    (net (code "31") (name "/K_Out_09") (class "Default")
      (node (ref "DP9") (pin "2") (pinfunction "K_2") (pintype "passive"))
      (node (ref "DX_9") (pin "2") (pintype "passive"))
      (node (ref "P_OUT") (pin "18") (pinfunction "18_18") (pintype "passive"))
      (node (ref "R27") (pin "2") (pinfunction "2_2") (pintype "passive"))
      (node (ref "RL_09") (pin "2") (pinfunction "2_2") (pintype "passive"))
    )
    (net (code "32") (name "/K_Out_10") (class "Default")
      (node (ref "DP10") (pin "2") (pinfunction "K_2") (pintype "passive"))
      (node (ref "DX_10") (pin "2") (pintype "passive"))
      (node (ref "P_OUT") (pin "19") (pinfunction "19_19") (pintype "passive"))
      (node (ref "R30") (pin "2") (pinfunction "2_2") (pintype "passive"))
      (node (ref "RL_10") (pin "2") (pinfunction "2_2") (pintype "passive"))
    )
    (net (code "33") (name "/K_Out_11") (class "Default")
      (node (ref "DP11") (pin "2") (pinfunction "K_2") (pintype "passive"))
      (node (ref "DX_11") (pin "2") (pintype "passive"))
      (node (ref "P_OUT") (pin "24") (pinfunction "24_24") (pintype "passive"))
      (node (ref "R33") (pin "2") (pinfunction "2_2") (pintype "passive"))
      (node (ref "RL_11") (pin "2") (pinfunction "2_2") (pintype "passive"))
    )
    (net (code "34") (name "/K_Out_12") (class "Default")
      (node (ref "DP12") (pin "2") (pinfunction "K_2") (pintype "passive"))
      (node (ref "DX_12") (pin "2") (pintype "passive"))
      (node (ref "P_OUT") (pin "12") (pinfunction "12_12") (pintype "passive"))
      (node (ref "R36") (pin "2") (pinfunction "2_2") (pintype "passive"))
      (node (ref "RL_12") (pin "2") (pinfunction "2_2") (pintype "passive"))
    )
    (net (code "35") (name "/K_Out_13") (class "Default")
      (node (ref "DP13") (pin "2") (pinfunction "K_2") (pintype "passive"))
      (node (ref "DX_13") (pin "2") (pintype "passive"))
      (node (ref "P_OUT") (pin "23") (pinfunction "23_23") (pintype "passive"))
      (node (ref "R39") (pin "2") (pinfunction "2_2") (pintype "passive"))
      (node (ref "RL_13") (pin "2") (pinfunction "2_2") (pintype "passive"))
    )
    (net (code "36") (name "/K_Out_14") (class "Default")
      (node (ref "DP14") (pin "2") (pinfunction "K_2") (pintype "passive"))
      (node (ref "DX_14") (pin "2") (pintype "passive"))
      (node (ref "P_OUT") (pin "11") (pinfunction "11_11") (pintype "passive"))
      (node (ref "R42") (pin "2") (pinfunction "2_2") (pintype "passive"))
      (node (ref "RL_14") (pin "2") (pinfunction "2_2") (pintype "passive"))
    )
    (net (code "37") (name "/K_Out_15") (class "Default")
      (node (ref "DP15") (pin "2") (pinfunction "K_2") (pintype "passive"))
      (node (ref "DX_15") (pin "2") (pintype "passive"))
      (node (ref "P_OUT") (pin "22") (pinfunction "22_22") (pintype "passive"))
      (node (ref "R45") (pin "2") (pinfunction "2_2") (pintype "passive"))
      (node (ref "RL_15") (pin "2") (pinfunction "2_2") (pintype "passive"))
    )
    (net (code "38") (name "/K_Out_16") (class "Default")
      (node (ref "DP16") (pin "2") (pinfunction "K_2") (pintype "passive"))
      (node (ref "DX_16") (pin "2") (pintype "passive"))
      (node (ref "P_OUT") (pin "10") (pinfunction "10_10") (pintype "passive"))
      (node (ref "R48") (pin "2") (pinfunction "2_2") (pintype "passive"))
      (node (ref "RL_16") (pin "2") (pinfunction "2_2") (pintype "passive"))
    )
    (net (code "39") (name "/K_Out_17") (class "Default")
      (node (ref "DP17") (pin "2") (pinfunction "K_2") (pintype "passive"))
      (node (ref "DX_17") (pin "2") (pintype "passive"))
      (node (ref "P_OUT") (pin "21") (pinfunction "21_21") (pintype "passive"))
      (node (ref "RL_17") (pin "2") (pinfunction "2_2") (pintype "passive"))
    )
    (net (code "40") (name "/K_Out_18") (class "Default")
      (node (ref "DP18") (pin "2") (pinfunction "K_2") (pintype "passive"))
      (node (ref "DX_18") (pin "2") (pintype "passive"))
      (node (ref "P_OUT") (pin "9") (pinfunction "9_9") (pintype "passive"))
      (node (ref "RL_18") (pin "2") (pinfunction "2_2") (pintype "passive"))
    )
    (net (code "41") (name "/K_Out_19") (class "Default")
      (node (ref "LED_19") (pin "K") (pintype "passive"))
      (node (ref "P_OUT") (pin "8") (pinfunction "8_8") (pintype "passive"))
      (node (ref "QP19") (pin "2") (pinfunction "D_2") (pintype "passive"))
    )
    (net (code "42") (name "/K_Out_20") (class "Default")
      (node (ref "LED_20") (pin "K") (pintype "passive"))
      (node (ref "P_OUT") (pin "20") (pinfunction "20_20") (pintype "passive"))
      (node (ref "QP20") (pin "2") (pinfunction "D_2") (pintype "passive"))
    )
    (net (code "43") (name "/K_Out_21") (class "Default")
      (node (ref "P_OUT") (pin "7") (pinfunction "7_7") (pintype "passive+no_connect"))
    )
    (net (code "44") (name "/K_Out_22") (class "Default")
      (node (ref "P_OUT") (pin "6") (pinfunction "6_6") (pintype "passive+no_connect"))
    )
    (net (code "45") (name "/K_Out_23") (class "Default")
      (node (ref "P_OUT") (pin "4") (pinfunction "4_4") (pintype "passive+no_connect"))
    )
    (net (code "46") (name "/K_Out_24") (class "Default")
      (node (ref "P_OUT") (pin "5") (pinfunction "5_5") (pintype "passive+no_connect"))
    )
    (net (code "47") (name "/PA0") (class "Default")
      (node (ref "R1") (pin "1") (pinfunction "1_1") (pintype "passive"))
      (node (ref "UIO") (pin "21") (pinfunction "PA0_21") (pintype "passive"))
    )
    (net (code "48") (name "/PA1") (class "Default")
      (node (ref "R4") (pin "1") (pinfunction "1_1") (pintype "passive"))
      (node (ref "UIO") (pin "22") (pinfunction "PA1_22") (pintype "passive"))
    )
    (net (code "49") (name "/PA2") (class "Default")
      (node (ref "R7") (pin "1") (pinfunction "1_1") (pintype "passive"))
      (node (ref "UIO") (pin "23") (pinfunction "PA2_23") (pintype "passive"))
    )
    (net (code "50") (name "/PA3") (class "Default")
      (node (ref "R10") (pin "1") (pinfunction "1_1") (pintype "passive"))
      (node (ref "UIO") (pin "24") (pinfunction "PA3_24") (pintype "passive"))
    )
    (net (code "51") (name "/PA4") (class "Default")
      (node (ref "R13") (pin "1") (pinfunction "1_1") (pintype "passive"))
      (node (ref "UIO") (pin "25") (pinfunction "PA4_25") (pintype "passive"))
    )
    (net (code "52") (name "/PA5") (class "Default")
      (node (ref "R16") (pin "1") (pinfunction "1_1") (pintype "passive"))
      (node (ref "UIO") (pin "26") (pinfunction "PA5_26") (pintype "passive"))
    )
    (net (code "53") (name "/PA6") (class "Default")
      (node (ref "R19") (pin "1") (pinfunction "1_1") (pintype "passive"))
      (node (ref "UIO") (pin "27") (pinfunction "PA6_27") (pintype "passive"))
    )
    (net (code "54") (name "/PA7") (class "Default")
      (node (ref "R22") (pin "1") (pinfunction "1_1") (pintype "passive"))
      (node (ref "UIO") (pin "28") (pinfunction "PA7_28") (pintype "passive"))
    )
    (net (code "55") (name "/PAX0") (class "Default")
      (node (ref "C00") (pin "2") (pinfunction "2_2") (pintype "passive"))
      (node (ref "ESD3") (pin "3") (pinfunction "I/O_3") (pintype "passive"))
      (node (ref "R1") (pin "2") (pinfunction "2_2") (pintype "passive"))
      (node (ref "R2") (pin "2") (pinfunction "2_2") (pintype "passive"))
      (node (ref "R3") (pin "1") (pinfunction "1_1") (pintype "passive"))
      (node (ref "ZM01") (pin "2") (pinfunction "K_2") (pintype "passive"))
    )
    (net (code "56") (name "/PAX1") (class "Default")
      (node (ref "C02") (pin "2") (pinfunction "2_2") (pintype "passive"))
      (node (ref "ESD1") (pin "3") (pinfunction "I/O_3") (pintype "passive"))
      (node (ref "R4") (pin "2") (pinfunction "2_2") (pintype "passive"))
      (node (ref "R5") (pin "2") (pinfunction "2_2") (pintype "passive"))
      (node (ref "R6") (pin "1") (pinfunction "1_1") (pintype "passive"))
      (node (ref "ZM02") (pin "2") (pinfunction "K_2") (pintype "passive"))
    )
    (net (code "57") (name "/PAX2") (class "Default")
      (node (ref "C03") (pin "2") (pinfunction "2_2") (pintype "passive"))
      (node (ref "ESD1") (pin "6") (pinfunction "I/O_6") (pintype "passive"))
      (node (ref "R7") (pin "2") (pinfunction "2_2") (pintype "passive"))
      (node (ref "R8") (pin "2") (pinfunction "2_2") (pintype "passive"))
      (node (ref "R9") (pin "1") (pinfunction "1_1") (pintype "passive"))
      (node (ref "ZM03") (pin "2") (pinfunction "K_2") (pintype "passive"))
    )
    (net (code "58") (name "/PAX3") (class "Default")
      (node (ref "C04") (pin "2") (pinfunction "2_2") (pintype "passive"))
      (node (ref "ESD1") (pin "4") (pinfunction "I/O_4") (pintype "passive"))
      (node (ref "R10") (pin "2") (pinfunction "2_2") (pintype "passive"))
      (node (ref "R11") (pin "2") (pinfunction "2_2") (pintype "passive"))
      (node (ref "R12") (pin "1") (pinfunction "1_1") (pintype "passive"))
      (node (ref "ZM04") (pin "2") (pinfunction "K_2") (pintype "passive"))
    )
    (net (code "59") (name "/PAX4") (class "Default")
      (node (ref "C05") (pin "2") (pinfunction "2_2") (pintype "passive"))
      (node (ref "ESD1") (pin "1") (pinfunction "I/O_1") (pintype "passive"))
      (node (ref "R13") (pin "2") (pinfunction "2_2") (pintype "passive"))
      (node (ref "R14") (pin "2") (pinfunction "2_2") (pintype "passive"))
      (node (ref "R15") (pin "1") (pinfunction "1_1") (pintype "passive"))
      (node (ref "ZM05") (pin "2") (pinfunction "K_2") (pintype "passive"))
    )
    (net (code "60") (name "/PAX5") (class "Default")
      (node (ref "C06") (pin "2") (pinfunction "2_2") (pintype "passive"))
      (node (ref "ESD3") (pin "1") (pinfunction "I/O_1") (pintype "passive"))
      (node (ref "R16") (pin "2") (pinfunction "2_2") (pintype "passive"))
      (node (ref "R17") (pin "2") (pinfunction "2_2") (pintype "passive"))
      (node (ref "R18") (pin "1") (pinfunction "1_1") (pintype "passive"))
      (node (ref "ZM06") (pin "2") (pinfunction "K_2") (pintype "passive"))
    )
    (net (code "61") (name "/PAX6") (class "Default")
      (node (ref "C07") (pin "2") (pinfunction "2_2") (pintype "passive"))
      (node (ref "ESD3") (pin "4") (pinfunction "I/O_4") (pintype "passive"))
      (node (ref "R19") (pin "2") (pinfunction "2_2") (pintype "passive"))
      (node (ref "R20") (pin "2") (pinfunction "2_2") (pintype "passive"))
      (node (ref "R21") (pin "1") (pinfunction "1_1") (pintype "passive"))
      (node (ref "ZM07") (pin "2") (pinfunction "K_2") (pintype "passive"))
    )
    (net (code "62") (name "/PAX7") (class "Default")
      (node (ref "C08") (pin "2") (pinfunction "2_2") (pintype "passive"))
      (node (ref "ESD3") (pin "6") (pinfunction "I/O_6") (pintype "passive"))
      (node (ref "R22") (pin "2") (pinfunction "2_2") (pintype "passive"))
      (node (ref "R23") (pin "2") (pinfunction "2_2") (pintype "passive"))
      (node (ref "R24") (pin "1") (pinfunction "1_1") (pintype "passive"))
      (node (ref "ZM08") (pin "2") (pinfunction "K_2") (pintype "passive"))
    )
    (net (code "63") (name "/PB0") (class "Default")
      (node (ref "R25") (pin "1") (pinfunction "1_1") (pintype "passive"))
      (node (ref "UIO") (pin "1") (pinfunction "PB0_1") (pintype "passive"))
    )
    (net (code "64") (name "/PB1") (class "Default")
      (node (ref "R28") (pin "1") (pinfunction "1_1") (pintype "passive"))
      (node (ref "UIO") (pin "2") (pinfunction "PB1_2") (pintype "passive"))
    )
    (net (code "65") (name "/PB2") (class "Default")
      (node (ref "R31") (pin "1") (pinfunction "1_1") (pintype "passive"))
      (node (ref "UIO") (pin "3") (pinfunction "PB2_3") (pintype "passive"))
    )
    (net (code "66") (name "/PB3") (class "Default")
      (node (ref "R34") (pin "1") (pinfunction "1_1") (pintype "passive"))
      (node (ref "UIO") (pin "4") (pinfunction "PB3_4") (pintype "passive"))
    )
    (net (code "67") (name "/PB4") (class "Default")
      (node (ref "R37") (pin "1") (pinfunction "1_1") (pintype "passive"))
      (node (ref "UIO") (pin "5") (pinfunction "PB4_5") (pintype "passive"))
    )
    (net (code "68") (name "/PB5") (class "Default")
      (node (ref "R40") (pin "1") (pinfunction "1_1") (pintype "passive"))
      (node (ref "UIO") (pin "6") (pinfunction "PB5_6") (pintype "passive"))
    )
    (net (code "69") (name "/PB6") (class "Default")
      (node (ref "R43") (pin "1") (pinfunction "1_1") (pintype "passive"))
      (node (ref "UIO") (pin "7") (pinfunction "PB6_7") (pintype "passive"))
    )
    (net (code "70") (name "/PB7") (class "Default")
      (node (ref "R46") (pin "1") (pinfunction "1_1") (pintype "passive"))
      (node (ref "UIO") (pin "8") (pinfunction "PB7_8") (pintype "passive"))
    )
    (net (code "71") (name "/PBX0") (class "Default")
      (node (ref "C09") (pin "2") (pinfunction "2_2") (pintype "passive"))
      (node (ref "ESD4") (pin "4") (pinfunction "I/O_4") (pintype "passive"))
      (node (ref "R25") (pin "2") (pinfunction "2_2") (pintype "passive"))
      (node (ref "R26") (pin "2") (pinfunction "2_2") (pintype "passive"))
      (node (ref "R27") (pin "1") (pinfunction "1_1") (pintype "passive"))
      (node (ref "ZM09") (pin "2") (pinfunction "K_2") (pintype "passive"))
    )
    (net (code "72") (name "/PBX1") (class "Default")
      (node (ref "C10") (pin "2") (pinfunction "2_2") (pintype "passive"))
      (node (ref "ESD4") (pin "6") (pinfunction "I/O_6") (pintype "passive"))
      (node (ref "R28") (pin "2") (pinfunction "2_2") (pintype "passive"))
      (node (ref "R29") (pin "2") (pinfunction "2_2") (pintype "passive"))
      (node (ref "R30") (pin "1") (pinfunction "1_1") (pintype "passive"))
      (node (ref "ZM10") (pin "2") (pinfunction "K_2") (pintype "passive"))
    )
    (net (code "73") (name "/PBX2") (class "Default")
      (node (ref "C11") (pin "2") (pinfunction "2_2") (pintype "passive"))
      (node (ref "ESD2") (pin "4") (pinfunction "I/O_4") (pintype "passive"))
      (node (ref "R31") (pin "2") (pinfunction "2_2") (pintype "passive"))
      (node (ref "R32") (pin "2") (pinfunction "2_2") (pintype "passive"))
      (node (ref "R33") (pin "1") (pinfunction "1_1") (pintype "passive"))
      (node (ref "ZM11") (pin "2") (pinfunction "K_2") (pintype "passive"))
    )
    (net (code "74") (name "/PBX3") (class "Default")
      (node (ref "C12") (pin "2") (pinfunction "2_2") (pintype "passive"))
      (node (ref "ESD2") (pin "6") (pinfunction "I/O_6") (pintype "passive"))
      (node (ref "R34") (pin "2") (pinfunction "2_2") (pintype "passive"))
      (node (ref "R35") (pin "2") (pinfunction "2_2") (pintype "passive"))
      (node (ref "R36") (pin "1") (pinfunction "1_1") (pintype "passive"))
      (node (ref "ZM12") (pin "2") (pinfunction "K_2") (pintype "passive"))
    )
    (net (code "75") (name "/PBX4") (class "Default")
      (node (ref "C13") (pin "2") (pinfunction "2_2") (pintype "passive"))
      (node (ref "ESD2") (pin "1") (pinfunction "I/O_1") (pintype "passive"))
      (node (ref "R37") (pin "2") (pinfunction "2_2") (pintype "passive"))
      (node (ref "R38") (pin "2") (pinfunction "2_2") (pintype "passive"))
      (node (ref "R39") (pin "1") (pinfunction "1_1") (pintype "passive"))
      (node (ref "ZM13") (pin "2") (pinfunction "K_2") (pintype "passive"))
    )
    (net (code "76") (name "/PBX5") (class "Default")
      (node (ref "C14") (pin "2") (pinfunction "2_2") (pintype "passive"))
      (node (ref "ESD2") (pin "3") (pinfunction "I/O_3") (pintype "passive"))
      (node (ref "R40") (pin "2") (pinfunction "2_2") (pintype "passive"))
      (node (ref "R41") (pin "2") (pinfunction "2_2") (pintype "passive"))
      (node (ref "R42") (pin "1") (pinfunction "1_1") (pintype "passive"))
      (node (ref "ZM14") (pin "2") (pinfunction "K_2") (pintype "passive"))
    )
    (net (code "77") (name "/PBX6") (class "Default")
      (node (ref "C15") (pin "2") (pinfunction "2_2") (pintype "passive"))
      (node (ref "ESD4") (pin "1") (pinfunction "I/O_1") (pintype "passive"))
      (node (ref "R43") (pin "2") (pinfunction "2_2") (pintype "passive"))
      (node (ref "R44") (pin "2") (pinfunction "2_2") (pintype "passive"))
      (node (ref "R45") (pin "1") (pinfunction "1_1") (pintype "passive"))
      (node (ref "ZM15") (pin "2") (pinfunction "K_2") (pintype "passive"))
    )
    (net (code "78") (name "/PBX7") (class "Default")
      (node (ref "C16") (pin "2") (pinfunction "2_2") (pintype "passive"))
      (node (ref "ESD4") (pin "3") (pinfunction "I/O_3") (pintype "passive"))
      (node (ref "R46") (pin "2") (pinfunction "2_2") (pintype "passive"))
      (node (ref "R47") (pin "2") (pinfunction "2_2") (pintype "passive"))
      (node (ref "R48") (pin "1") (pinfunction "1_1") (pintype "passive"))
      (node (ref "ZM16") (pin "2") (pinfunction "K_2") (pintype "passive"))
    )
    (net (code "79") (name "/SCL") (class "Default")
      (node (ref "JR") (pin "25") (pinfunction "25_25") (pintype "passive"))
      (node (ref "RI8") (pin "1") (pinfunction "1_1") (pintype "passive"))
    )
    (net (code "80") (name "/SDA") (class "Default")
      (node (ref "JR") (pin "26") (pinfunction "26_26") (pintype "passive"))
      (node (ref "RI9") (pin "1") (pinfunction "1_1") (pintype "passive"))
    )
    (net (code "81") (name "Net-(CA2-Pad2)") (class "Default")
      (node (ref "CA2") (pin "2") (pinfunction "2_2") (pintype "passive"))
      (node (ref "CA4") (pin "1") (pinfunction "1_1") (pintype "passive"))
      (node (ref "LA1") (pin "2") (pinfunction "2_2") (pintype "passive"))
      (node (ref "RA4") (pin "2") (pinfunction "2_2") (pintype "passive"))
      (node (ref "RA8") (pin "1") (pinfunction "1_1") (pintype "passive"))
    )
    (net (code "82") (name "Net-(CB2-Pad2)") (class "Default")
      (node (ref "CB2") (pin "2") (pinfunction "2_2") (pintype "passive"))
      (node (ref "CB4") (pin "1") (pinfunction "1_1") (pintype "passive"))
      (node (ref "LB1") (pin "2") (pinfunction "2_2") (pintype "passive"))
      (node (ref "RB4") (pin "2") (pinfunction "2_2") (pintype "passive"))
      (node (ref "RB8") (pin "1") (pinfunction "1_1") (pintype "passive"))
    )
    (net (code "83") (name "Net-(D1-2-K)") (class "Default")
      (node (ref "D1-2") (pin "2") (pinfunction "K_2") (pintype "passive"))
      (node (ref "R1-2") (pin "2") (pinfunction "2_2") (pintype "passive"))
    )
    (net (code "84") (name "Net-(D3-4-K)") (class "Default")
      (node (ref "D3-4") (pin "2") (pinfunction "K_2") (pintype "passive"))
      (node (ref "R3-4") (pin "2") (pinfunction "2_2") (pintype "passive"))
    )
    (net (code "85") (name "Net-(D5-6-K)") (class "Default")
      (node (ref "D5-6") (pin "2") (pinfunction "K_2") (pintype "passive"))
      (node (ref "R5-6") (pin "2") (pinfunction "2_2") (pintype "passive"))
    )
    (net (code "86") (name "Net-(D7-8-K)") (class "Default")
      (node (ref "D7-8") (pin "2") (pinfunction "K_2") (pintype "passive"))
      (node (ref "R7-8") (pin "2") (pinfunction "2_2") (pintype "passive"))
    )
    (net (code "87") (name "Net-(D9-10-K)") (class "Default")
      (node (ref "D9-10") (pin "2") (pinfunction "K_2") (pintype "passive"))
      (node (ref "R9-10") (pin "2") (pinfunction "2_2") (pintype "passive"))
    )
    (net (code "88") (name "Net-(D11-12-K)") (class "Default")
      (node (ref "D11-12") (pin "2") (pinfunction "K_2") (pintype "passive"))
      (node (ref "R11-12") (pin "2") (pinfunction "2_2") (pintype "passive"))
    )
    (net (code "89") (name "Net-(D13-14-K)") (class "Default")
      (node (ref "D13-14") (pin "2") (pinfunction "K_2") (pintype "passive"))
      (node (ref "R13-14") (pin "2") (pinfunction "2_2") (pintype "passive"))
    )
    (net (code "90") (name "Net-(D15-16-K)") (class "Default")
      (node (ref "D15-16") (pin "2") (pinfunction "K_2") (pintype "passive"))
      (node (ref "R15-16") (pin "2") (pinfunction "2_2") (pintype "passive"))
    )
    (net (code "91") (name "Net-(D17-18-K)") (class "Default")
      (node (ref "D17-18") (pin "2") (pinfunction "K_2") (pintype "passive"))
      (node (ref "R17-18") (pin "2") (pinfunction "2_2") (pintype "passive"))
    )
    (net (code "92") (name "Net-(DP1-A)") (class "Default")
      (node (ref "DP1") (pin "1") (pinfunction "A_1") (pintype "passive"))
      (node (ref "QP1") (pin "3") (pinfunction "S_3") (pintype "passive"))
      (node (ref "ZD1") (pin "1") (pintype "passive"))
    )
    (net (code "93") (name "Net-(DP2-A)") (class "Default")
      (node (ref "DP2") (pin "1") (pinfunction "A_1") (pintype "passive"))
      (node (ref "QP2") (pin "3") (pinfunction "S_3") (pintype "passive"))
      (node (ref "ZD2") (pin "1") (pintype "passive"))
    )
    (net (code "94") (name "Net-(DP3-A)") (class "Default")
      (node (ref "DP3") (pin "1") (pinfunction "A_1") (pintype "passive"))
      (node (ref "QP3") (pin "3") (pinfunction "S_3") (pintype "passive"))
      (node (ref "ZD3") (pin "1") (pintype "passive"))
    )
    (net (code "95") (name "Net-(DP4-A)") (class "Default")
      (node (ref "DP4") (pin "1") (pinfunction "A_1") (pintype "passive"))
      (node (ref "QP4") (pin "3") (pinfunction "S_3") (pintype "passive"))
      (node (ref "ZD4") (pin "1") (pintype "passive"))
    )
    (net (code "96") (name "Net-(DP5-A)") (class "Default")
      (node (ref "DP5") (pin "1") (pinfunction "A_1") (pintype "passive"))
      (node (ref "QP5") (pin "3") (pinfunction "S_3") (pintype "passive"))
      (node (ref "ZD5") (pin "1") (pintype "passive"))
    )
    (net (code "97") (name "Net-(DP6-A)") (class "Default")
      (node (ref "DP6") (pin "1") (pinfunction "A_1") (pintype "passive"))
      (node (ref "QP6") (pin "3") (pinfunction "S_3") (pintype "passive"))
      (node (ref "ZD6") (pin "1") (pintype "passive"))
    )
    (net (code "98") (name "Net-(DP7-A)") (class "Default")
      (node (ref "DP7") (pin "1") (pinfunction "A_1") (pintype "passive"))
      (node (ref "QP7") (pin "3") (pinfunction "S_3") (pintype "passive"))
      (node (ref "ZD7") (pin "1") (pintype "passive"))
    )
    (net (code "99") (name "Net-(DP8-A)") (class "Default")
      (node (ref "DP8") (pin "1") (pinfunction "A_1") (pintype "passive"))
      (node (ref "QP8") (pin "3") (pinfunction "S_3") (pintype "passive"))
      (node (ref "ZD8") (pin "1") (pintype "passive"))
    )
    (net (code "100") (name "Net-(DP9-A)") (class "Default")
      (node (ref "DP9") (pin "1") (pinfunction "A_1") (pintype "passive"))
      (node (ref "QP9") (pin "3") (pinfunction "S_3") (pintype "passive"))
      (node (ref "ZD9") (pin "1") (pintype "passive"))
    )
    (net (code "101") (name "Net-(DP10-A)") (class "Default")
      (node (ref "DP10") (pin "1") (pinfunction "A_1") (pintype "passive"))
      (node (ref "QP10") (pin "3") (pinfunction "S_3") (pintype "passive"))
      (node (ref "ZD10") (pin "1") (pintype "passive"))
    )
    (net (code "102") (name "Net-(DP11-A)") (class "Default")
      (node (ref "DP11") (pin "1") (pinfunction "A_1") (pintype "passive"))
      (node (ref "QP11") (pin "3") (pinfunction "S_3") (pintype "passive"))
      (node (ref "ZD11") (pin "1") (pintype "passive"))
    )
    (net (code "103") (name "Net-(DP12-A)") (class "Default")
      (node (ref "DP12") (pin "1") (pinfunction "A_1") (pintype "passive"))
      (node (ref "QP12") (pin "3") (pinfunction "S_3") (pintype "passive"))
      (node (ref "ZD12") (pin "1") (pintype "passive"))
    )
    (net (code "104") (name "Net-(DP13-A)") (class "Default")
      (node (ref "DP13") (pin "1") (pinfunction "A_1") (pintype "passive"))
      (node (ref "QP13") (pin "3") (pinfunction "S_3") (pintype "passive"))
      (node (ref "ZD13") (pin "1") (pintype "passive"))
    )
    (net (code "105") (name "Net-(DP14-A)") (class "Default")
      (node (ref "DP14") (pin "1") (pinfunction "A_1") (pintype "passive"))
      (node (ref "QP14") (pin "3") (pinfunction "S_3") (pintype "passive"))
      (node (ref "ZD14") (pin "1") (pintype "passive"))
    )
    (net (code "106") (name "Net-(DP15-A)") (class "Default")
      (node (ref "DP15") (pin "1") (pinfunction "A_1") (pintype "passive"))
      (node (ref "QP15") (pin "3") (pinfunction "S_3") (pintype "passive"))
      (node (ref "ZD15") (pin "1") (pintype "passive"))
    )
    (net (code "107") (name "Net-(DP16-A)") (class "Default")
      (node (ref "DP16") (pin "1") (pinfunction "A_1") (pintype "passive"))
      (node (ref "QP16") (pin "3") (pinfunction "S_3") (pintype "passive"))
      (node (ref "ZD16") (pin "1") (pintype "passive"))
    )
    (net (code "108") (name "Net-(DP17-A)") (class "Default")
      (node (ref "DP17") (pin "1") (pinfunction "A_1") (pintype "passive"))
      (node (ref "QP17") (pin "3") (pinfunction "S_3") (pintype "passive"))
      (node (ref "ZD17") (pin "1") (pintype "passive"))
    )
    (net (code "109") (name "Net-(DP18-A)") (class "Default")
      (node (ref "DP18") (pin "1") (pinfunction "A_1") (pintype "passive"))
      (node (ref "QP18") (pin "3") (pinfunction "S_3") (pintype "passive"))
      (node (ref "ZD18") (pin "1") (pintype "passive"))
    )
    (net (code "110") (name "Net-(JR-Pad23)") (class "Default")
      (node (ref "JR") (pin "23") (pinfunction "23_23") (pintype "passive"))
      (node (ref "R_J5V") (pin "2") (pinfunction "2_2") (pintype "passive"))
    )
    (net (code "111") (name "Net-(LED_01-PadA)") (class "Default")
      (node (ref "LED_01") (pin "A") (pintype "passive"))
      (node (ref "RL_01") (pin "1") (pinfunction "1_1") (pintype "passive"))
    )
    (net (code "112") (name "Net-(LED_02-PadA)") (class "Default")
      (node (ref "LED_02") (pin "A") (pintype "passive"))
      (node (ref "RL_02") (pin "1") (pinfunction "1_1") (pintype "passive"))
    )
    (net (code "113") (name "Net-(LED_03-PadA)") (class "Default")
      (node (ref "LED_03") (pin "A") (pintype "passive"))
      (node (ref "RL_03") (pin "1") (pinfunction "1_1") (pintype "passive"))
    )
    (net (code "114") (name "Net-(LED_04-PadA)") (class "Default")
      (node (ref "LED_04") (pin "A") (pintype "passive"))
      (node (ref "RL_04") (pin "1") (pinfunction "1_1") (pintype "passive"))
    )
    (net (code "115") (name "Net-(LED_05-PadA)") (class "Default")
      (node (ref "LED_05") (pin "A") (pintype "passive"))
      (node (ref "RL_05") (pin "1") (pinfunction "1_1") (pintype "passive"))
    )
    (net (code "116") (name "Net-(LED_06-PadA)") (class "Default")
      (node (ref "LED_06") (pin "A") (pintype "passive"))
      (node (ref "RL_06") (pin "1") (pinfunction "1_1") (pintype "passive"))
    )
    (net (code "117") (name "Net-(LED_07-PadA)") (class "Default")
      (node (ref "LED_07") (pin "A") (pintype "passive"))
      (node (ref "RL_07") (pin "1") (pinfunction "1_1") (pintype "passive"))
    )
    (net (code "118") (name "Net-(LED_08-PadA)") (class "Default")
      (node (ref "LED_08") (pin "A") (pintype "passive"))
      (node (ref "RL_08") (pin "1") (pinfunction "1_1") (pintype "passive"))
    )
    (net (code "119") (name "Net-(LED_09-PadA)") (class "Default")
      (node (ref "LED_09") (pin "A") (pintype "passive"))
      (node (ref "RL_09") (pin "1") (pinfunction "1_1") (pintype "passive"))
    )
    (net (code "120") (name "Net-(LED_10-PadA)") (class "Default")
      (node (ref "LED_10") (pin "A") (pintype "passive"))
      (node (ref "RL_10") (pin "1") (pinfunction "1_1") (pintype "passive"))
    )
    (net (code "121") (name "Net-(LED_11-PadA)") (class "Default")
      (node (ref "LED_11") (pin "A") (pintype "passive"))
      (node (ref "RL_11") (pin "1") (pinfunction "1_1") (pintype "passive"))
    )
    (net (code "122") (name "Net-(LED_12-PadA)") (class "Default")
      (node (ref "LED_12") (pin "A") (pintype "passive"))
      (node (ref "RL_12") (pin "1") (pinfunction "1_1") (pintype "passive"))
    )
    (net (code "123") (name "Net-(LED_13-PadA)") (class "Default")
      (node (ref "LED_13") (pin "A") (pintype "passive"))
      (node (ref "RL_13") (pin "1") (pinfunction "1_1") (pintype "passive"))
    )
    (net (code "124") (name "Net-(LED_14-PadA)") (class "Default")
      (node (ref "LED_14") (pin "A") (pintype "passive"))
      (node (ref "RL_14") (pin "1") (pinfunction "1_1") (pintype "passive"))
    )
    (net (code "125") (name "Net-(LED_15-PadA)") (class "Default")
      (node (ref "LED_15") (pin "A") (pintype "passive"))
      (node (ref "RL_15") (pin "1") (pinfunction "1_1") (pintype "passive"))
    )
    (net (code "126") (name "Net-(LED_16-PadA)") (class "Default")
      (node (ref "LED_16") (pin "A") (pintype "passive"))
      (node (ref "RL_16") (pin "1") (pinfunction "1_1") (pintype "passive"))
    )
    (net (code "127") (name "Net-(LED_17-PadA)") (class "Default")
      (node (ref "LED_17") (pin "A") (pintype "passive"))
      (node (ref "RL_17") (pin "1") (pinfunction "1_1") (pintype "passive"))
    )
    (net (code "128") (name "Net-(LED_18-PadA)") (class "Default")
      (node (ref "LED_18") (pin "A") (pintype "passive"))
      (node (ref "RL_18") (pin "1") (pinfunction "1_1") (pintype "passive"))
    )
    (net (code "129") (name "Net-(LED_19-PadA)") (class "Default")
      (node (ref "LED_19") (pin "A") (pintype "passive"))
      (node (ref "RL_19") (pin "1") (pinfunction "1_1") (pintype "passive"))
    )
    (net (code "130") (name "Net-(LED_20-PadA)") (class "Default")
      (node (ref "LED_20") (pin "A") (pintype "passive"))
      (node (ref "RL_20") (pin "1") (pinfunction "1_1") (pintype "passive"))
    )
    (net (code "131") (name "Net-(QP1-D)") (class "Default")
      (node (ref "CQ1") (pin "1") (pintype "passive"))
      (node (ref "QP1") (pin "2") (pinfunction "D_2") (pintype "passive"))
      (node (ref "RQ1") (pin "1") (pinfunction "1_1") (pintype "passive"))
      (node (ref "U1-2") (pin "1") (pinfunction "DS1_1") (pintype "passive"))
    )
    (net (code "132") (name "Net-(QP1-G)") (class "Default")
      (node (ref "QP1") (pin "1") (pinfunction "G_1") (pintype "passive"))
      (node (ref "U1-2") (pin "2") (pinfunction "G1_2") (pintype "passive"))
      (node (ref "ZD1") (pin "2") (pintype "passive"))
    )
    (net (code "133") (name "Net-(QP2-D)") (class "Default")
      (node (ref "CQ2") (pin "1") (pintype "passive"))
      (node (ref "QP2") (pin "2") (pinfunction "D_2") (pintype "passive"))
      (node (ref "RQ2") (pin "2") (pinfunction "2_2") (pintype "passive"))
      (node (ref "U1-2") (pin "8") (pinfunction "DS2_8") (pintype "passive"))
    )
    (net (code "134") (name "Net-(QP2-G)") (class "Default")
      (node (ref "QP2") (pin "1") (pinfunction "G_1") (pintype "passive"))
      (node (ref "U1-2") (pin "7") (pinfunction "G2_7") (pintype "passive"))
      (node (ref "ZD2") (pin "2") (pintype "passive"))
    )
    (net (code "135") (name "Net-(QP3-D)") (class "Default")
      (node (ref "CQ3") (pin "1") (pintype "passive"))
      (node (ref "QP3") (pin "2") (pinfunction "D_2") (pintype "passive"))
      (node (ref "RQ3") (pin "1") (pinfunction "1_1") (pintype "passive"))
      (node (ref "U3-4") (pin "1") (pinfunction "DS1_1") (pintype "passive"))
    )
    (net (code "136") (name "Net-(QP3-G)") (class "Default")
      (node (ref "QP3") (pin "1") (pinfunction "G_1") (pintype "passive"))
      (node (ref "U3-4") (pin "2") (pinfunction "G1_2") (pintype "passive"))
      (node (ref "ZD3") (pin "2") (pintype "passive"))
    )
    (net (code "137") (name "Net-(QP4-D)") (class "Default")
      (node (ref "CQ4") (pin "1") (pintype "passive"))
      (node (ref "QP4") (pin "2") (pinfunction "D_2") (pintype "passive"))
      (node (ref "RQ4") (pin "2") (pinfunction "2_2") (pintype "passive"))
      (node (ref "U3-4") (pin "8") (pinfunction "DS2_8") (pintype "passive"))
    )
    (net (code "138") (name "Net-(QP4-G)") (class "Default")
      (node (ref "QP4") (pin "1") (pinfunction "G_1") (pintype "passive"))
      (node (ref "U3-4") (pin "7") (pinfunction "G2_7") (pintype "passive"))
      (node (ref "ZD4") (pin "2") (pintype "passive"))
    )
    (net (code "139") (name "Net-(QP5-D)") (class "Default")
      (node (ref "CQ5") (pin "1") (pintype "passive"))
      (node (ref "QP5") (pin "2") (pinfunction "D_2") (pintype "passive"))
      (node (ref "RQ5") (pin "1") (pinfunction "1_1") (pintype "passive"))
      (node (ref "U5-6") (pin "1") (pinfunction "DS1_1") (pintype "passive"))
    )
    (net (code "140") (name "Net-(QP5-G)") (class "Default")
      (node (ref "QP5") (pin "1") (pinfunction "G_1") (pintype "passive"))
      (node (ref "U5-6") (pin "2") (pinfunction "G1_2") (pintype "passive"))
      (node (ref "ZD5") (pin "2") (pintype "passive"))
    )
    (net (code "141") (name "Net-(QP6-D)") (class "Default")
      (node (ref "CQ6") (pin "1") (pintype "passive"))
      (node (ref "QP6") (pin "2") (pinfunction "D_2") (pintype "passive"))
      (node (ref "RQ6") (pin "2") (pinfunction "2_2") (pintype "passive"))
      (node (ref "U5-6") (pin "8") (pinfunction "DS2_8") (pintype "passive"))
    )
    (net (code "142") (name "Net-(QP6-G)") (class "Default")
      (node (ref "QP6") (pin "1") (pinfunction "G_1") (pintype "passive"))
      (node (ref "U5-6") (pin "7") (pinfunction "G2_7") (pintype "passive"))
      (node (ref "ZD6") (pin "2") (pintype "passive"))
    )
    (net (code "143") (name "Net-(QP7-D)") (class "Default")
      (node (ref "CQ7") (pin "1") (pintype "passive"))
      (node (ref "QP7") (pin "2") (pinfunction "D_2") (pintype "passive"))
      (node (ref "RQ7") (pin "1") (pinfunction "1_1") (pintype "passive"))
      (node (ref "U7-8") (pin "1") (pinfunction "DS1_1") (pintype "passive"))
    )
    (net (code "144") (name "Net-(QP7-G)") (class "Default")
      (node (ref "QP7") (pin "1") (pinfunction "G_1") (pintype "passive"))
      (node (ref "U7-8") (pin "2") (pinfunction "G1_2") (pintype "passive"))
      (node (ref "ZD7") (pin "2") (pintype "passive"))
    )
    (net (code "145") (name "Net-(QP8-D)") (class "Default")
      (node (ref "CQ8") (pin "1") (pintype "passive"))
      (node (ref "QP8") (pin "2") (pinfunction "D_2") (pintype "passive"))
      (node (ref "RQ8") (pin "2") (pinfunction "2_2") (pintype "passive"))
      (node (ref "U7-8") (pin "8") (pinfunction "DS2_8") (pintype "passive"))
    )
    (net (code "146") (name "Net-(QP8-G)") (class "Default")
      (node (ref "QP8") (pin "1") (pinfunction "G_1") (pintype "passive"))
      (node (ref "U7-8") (pin "7") (pinfunction "G2_7") (pintype "passive"))
      (node (ref "ZD8") (pin "2") (pintype "passive"))
    )
    (net (code "147") (name "Net-(QP9-D)") (class "Default")
      (node (ref "CQ9") (pin "1") (pintype "passive"))
      (node (ref "QP9") (pin "2") (pinfunction "D_2") (pintype "passive"))
      (node (ref "RQ9") (pin "1") (pinfunction "1_1") (pintype "passive"))
      (node (ref "U9-10") (pin "1") (pinfunction "DS1_1") (pintype "passive"))
    )
    (net (code "148") (name "Net-(QP9-G)") (class "Default")
      (node (ref "QP9") (pin "1") (pinfunction "G_1") (pintype "passive"))
      (node (ref "U9-10") (pin "2") (pinfunction "G1_2") (pintype "passive"))
      (node (ref "ZD9") (pin "2") (pintype "passive"))
    )
    (net (code "149") (name "Net-(QP10-D)") (class "Default")
      (node (ref "CQ10") (pin "1") (pintype "passive"))
      (node (ref "QP10") (pin "2") (pinfunction "D_2") (pintype "passive"))
      (node (ref "RQ10") (pin "2") (pinfunction "2_2") (pintype "passive"))
      (node (ref "U9-10") (pin "8") (pinfunction "DS2_8") (pintype "passive"))
    )
    (net (code "150") (name "Net-(QP10-G)") (class "Default")
      (node (ref "QP10") (pin "1") (pinfunction "G_1") (pintype "passive"))
      (node (ref "U9-10") (pin "7") (pinfunction "G2_7") (pintype "passive"))
      (node (ref "ZD10") (pin "2") (pintype "passive"))
    )
    (net (code "151") (name "Net-(QP11-D)") (class "Default")
      (node (ref "CQ11") (pin "1") (pintype "passive"))
      (node (ref "QP11") (pin "2") (pinfunction "D_2") (pintype "passive"))
      (node (ref "RQ11") (pin "1") (pinfunction "1_1") (pintype "passive"))
      (node (ref "U11-12") (pin "1") (pinfunction "DS1_1") (pintype "passive"))
    )
    (net (code "152") (name "Net-(QP11-G)") (class "Default")
      (node (ref "QP11") (pin "1") (pinfunction "G_1") (pintype "passive"))
      (node (ref "U11-12") (pin "2") (pinfunction "G1_2") (pintype "passive"))
      (node (ref "ZD11") (pin "2") (pintype "passive"))
    )
    (net (code "153") (name "Net-(QP12-D)") (class "Default")
      (node (ref "CQ12") (pin "1") (pintype "passive"))
      (node (ref "QP12") (pin "2") (pinfunction "D_2") (pintype "passive"))
      (node (ref "RQ12") (pin "2") (pinfunction "2_2") (pintype "passive"))
      (node (ref "U11-12") (pin "8") (pinfunction "DS2_8") (pintype "passive"))
    )
    (net (code "154") (name "Net-(QP12-G)") (class "Default")
      (node (ref "QP12") (pin "1") (pinfunction "G_1") (pintype "passive"))
      (node (ref "U11-12") (pin "7") (pinfunction "G2_7") (pintype "passive"))
      (node (ref "ZD12") (pin "2") (pintype "passive"))
    )
    (net (code "155") (name "Net-(QP13-D)") (class "Default")
      (node (ref "CQ13") (pin "1") (pintype "passive"))
      (node (ref "QP13") (pin "2") (pinfunction "D_2") (pintype "passive"))
      (node (ref "RQ13") (pin "1") (pinfunction "1_1") (pintype "passive"))
      (node (ref "U13-14") (pin "1") (pinfunction "DS1_1") (pintype "passive"))
    )
    (net (code "156") (name "Net-(QP13-G)") (class "Default")
      (node (ref "QP13") (pin "1") (pinfunction "G_1") (pintype "passive"))
      (node (ref "U13-14") (pin "2") (pinfunction "G1_2") (pintype "passive"))
      (node (ref "ZD13") (pin "2") (pintype "passive"))
    )
    (net (code "157") (name "Net-(QP14-D)") (class "Default")
      (node (ref "CQ14") (pin "1") (pintype "passive"))
      (node (ref "QP14") (pin "2") (pinfunction "D_2") (pintype "passive"))
      (node (ref "RQ14") (pin "2") (pinfunction "2_2") (pintype "passive"))
      (node (ref "U13-14") (pin "8") (pinfunction "DS2_8") (pintype "passive"))
    )
    (net (code "158") (name "Net-(QP14-G)") (class "Default")
      (node (ref "QP14") (pin "1") (pinfunction "G_1") (pintype "passive"))
      (node (ref "U13-14") (pin "7") (pinfunction "G2_7") (pintype "passive"))
      (node (ref "ZD14") (pin "2") (pintype "passive"))
    )
    (net (code "159") (name "Net-(QP15-D)") (class "Default")
      (node (ref "CQ15") (pin "1") (pintype "passive"))
      (node (ref "QP15") (pin "2") (pinfunction "D_2") (pintype "passive"))
      (node (ref "RQ15") (pin "1") (pinfunction "1_1") (pintype "passive"))
      (node (ref "U15-16") (pin "1") (pinfunction "DS1_1") (pintype "passive"))
    )
    (net (code "160") (name "Net-(QP15-G)") (class "Default")
      (node (ref "QP15") (pin "1") (pinfunction "G_1") (pintype "passive"))
      (node (ref "U15-16") (pin "2") (pinfunction "G1_2") (pintype "passive"))
      (node (ref "ZD15") (pin "2") (pintype "passive"))
    )
    (net (code "161") (name "Net-(QP16-D)") (class "Default")
      (node (ref "CQ16") (pin "1") (pintype "passive"))
      (node (ref "QP16") (pin "2") (pinfunction "D_2") (pintype "passive"))
      (node (ref "RQ16") (pin "2") (pinfunction "2_2") (pintype "passive"))
      (node (ref "U15-16") (pin "8") (pinfunction "DS2_8") (pintype "passive"))
    )
    (net (code "162") (name "Net-(QP16-G)") (class "Default")
      (node (ref "QP16") (pin "1") (pinfunction "G_1") (pintype "passive"))
      (node (ref "U15-16") (pin "7") (pinfunction "G2_7") (pintype "passive"))
      (node (ref "ZD16") (pin "2") (pintype "passive"))
    )
    (net (code "163") (name "Net-(QP17-D)") (class "Default")
      (node (ref "CQ17") (pin "1") (pintype "passive"))
      (node (ref "QP17") (pin "2") (pinfunction "D_2") (pintype "passive"))
      (node (ref "RQ17") (pin "1") (pinfunction "1_1") (pintype "passive"))
      (node (ref "U17-18") (pin "1") (pinfunction "DS1_1") (pintype "passive"))
    )
    (net (code "164") (name "Net-(QP17-G)") (class "Default")
      (node (ref "QP17") (pin "1") (pinfunction "G_1") (pintype "passive"))
      (node (ref "U17-18") (pin "2") (pinfunction "G1_2") (pintype "passive"))
      (node (ref "ZD17") (pin "2") (pintype "passive"))
    )
    (net (code "165") (name "Net-(QP18-D)") (class "Default")
      (node (ref "CQ18") (pin "1") (pintype "passive"))
      (node (ref "QP18") (pin "2") (pinfunction "D_2") (pintype "passive"))
      (node (ref "RQ18") (pin "2") (pinfunction "2_2") (pintype "passive"))
      (node (ref "U17-18") (pin "8") (pinfunction "DS2_8") (pintype "passive"))
    )
    (net (code "166") (name "Net-(QP18-G)") (class "Default")
      (node (ref "QP18") (pin "1") (pinfunction "G_1") (pintype "passive"))
      (node (ref "U17-18") (pin "7") (pinfunction "G2_7") (pintype "passive"))
      (node (ref "ZD18") (pin "2") (pintype "passive"))
    )
    (net (code "167") (name "Net-(QP19-G)") (class "Default")
      (node (ref "QP19") (pin "1") (pinfunction "G_1") (pintype "passive"))
      (node (ref "U24") (pin "7") (pinfunction "O_A_7") (pintype "passive"))
      (node (ref "ZD19") (pin "2") (pintype "passive"))
    )
    (net (code "168") (name "Net-(QP20-G)") (class "Default")
      (node (ref "QP20") (pin "1") (pinfunction "G_1") (pintype "passive"))
      (node (ref "U24") (pin "5") (pinfunction "O_B_5") (pintype "passive"))
      (node (ref "ZD20") (pin "2") (pintype "passive"))
    )
    (net (code "169") (name "Net-(RA2-Pad2)") (class "Default")
      (node (ref "RA2") (pin "2") (pinfunction "2_2") (pintype "passive"))
      (node (ref "RA3") (pin "1") (pinfunction "1_1") (pintype "passive"))
    )
    (net (code "170") (name "Net-(RA3-Pad2)") (class "Default")
      (node (ref "RA3") (pin "2") (pinfunction "2_2") (pintype "passive"))
      (node (ref "RA4") (pin "1") (pinfunction "1_1") (pintype "passive"))
    )
    (net (code "171") (name "Net-(RA5-Pad2)") (class "Default")
      (node (ref "RA5") (pin "2") (pinfunction "2_2") (pintype "passive"))
      (node (ref "RA6") (pin "1") (pinfunction "1_1") (pintype "passive"))
    )
    (net (code "172") (name "Net-(RA6-Pad2)") (class "Default")
      (node (ref "RA6") (pin "2") (pinfunction "2_2") (pintype "passive"))
      (node (ref "RA7") (pin "1") (pinfunction "1_1") (pintype "passive"))
    )
    (net (code "173") (name "Net-(RB2-Pad2)") (class "Default")
      (node (ref "RB2") (pin "2") (pinfunction "2_2") (pintype "passive"))
      (node (ref "RB3") (pin "1") (pinfunction "1_1") (pintype "passive"))
    )
    (net (code "174") (name "Net-(RB3-Pad2)") (class "Default")
      (node (ref "RB3") (pin "2") (pinfunction "2_2") (pintype "passive"))
      (node (ref "RB4") (pin "1") (pinfunction "1_1") (pintype "passive"))
    )
    (net (code "175") (name "Net-(RB5-Pad2)") (class "Default")
      (node (ref "RB5") (pin "2") (pinfunction "2_2") (pintype "passive"))
      (node (ref "RB6") (pin "1") (pinfunction "1_1") (pintype "passive"))
    )
    (net (code "176") (name "Net-(RB6-Pad2)") (class "Default")
      (node (ref "RB6") (pin "2") (pinfunction "2_2") (pintype "passive"))
      (node (ref "RB7") (pin "1") (pinfunction "1_1") (pintype "passive"))
    )
    (net (code "177") (name "Net-(SA1-K)") (class "Default")
      (node (ref "CA1") (pin "2") (pinfunction "2_2") (pintype "passive"))
      (node (ref "LA1") (pin "1") (pinfunction "1_1") (pintype "passive"))
      (node (ref "SA1") (pin "2") (pinfunction "K_2") (pintype "passive"))
      (node (ref "U-05") (pin "6") (pinfunction "SW_6") (pintype "passive"))
    )
    (net (code "178") (name "Net-(SB1-K)") (class "Default")
      (node (ref "CB1") (pin "2") (pinfunction "2_2") (pintype "passive"))
      (node (ref "LB1") (pin "1") (pinfunction "1_1") (pintype "passive"))
      (node (ref "SB1") (pin "2") (pinfunction "K_2") (pintype "passive"))
      (node (ref "U-12") (pin "6") (pinfunction "SW_6") (pintype "passive"))
    )
    (net (code "179") (name "Net-(U-05-BST)") (class "Default")
      (node (ref "CA1") (pin "1") (pinfunction "1_1") (pintype "passive"))
      (node (ref "U-05") (pin "1") (pinfunction "BST_1") (pintype "passive"))
    )
    (net (code "180") (name "Net-(U-05-EN)") (class "Default")
      (node (ref "RA1") (pin "1") (pinfunction "1_1") (pintype "passive"))
      (node (ref "U-05") (pin "4") (pinfunction "EN_4") (pintype "passive"))
    )
    (net (code "181") (name "Net-(U-05-FB)") (class "Default")
      (node (ref "CA2") (pin "1") (pinfunction "1_1") (pintype "passive"))
      (node (ref "RA2") (pin "1") (pinfunction "1_1") (pintype "passive"))
      (node (ref "RA5") (pin "1") (pinfunction "1_1") (pintype "passive"))
      (node (ref "U-05") (pin "3") (pinfunction "FB_3") (pintype "passive"))
    )
    (net (code "182") (name "Net-(U-12-BST)") (class "Default")
      (node (ref "CB1") (pin "1") (pinfunction "1_1") (pintype "passive"))
      (node (ref "U-12") (pin "1") (pinfunction "BST_1") (pintype "passive"))
    )
    (net (code "183") (name "Net-(U-12-EN)") (class "Default")
      (node (ref "RB1") (pin "1") (pinfunction "1_1") (pintype "passive"))
      (node (ref "U-12") (pin "4") (pinfunction "EN_4") (pintype "passive"))
    )
    (net (code "184") (name "Net-(U-12-FB)") (class "Default")
      (node (ref "CB2") (pin "1") (pinfunction "1_1") (pintype "passive"))
      (node (ref "RB2") (pin "1") (pinfunction "1_1") (pintype "passive"))
      (node (ref "RB5") (pin "1") (pinfunction "1_1") (pintype "passive"))
      (node (ref "U-12") (pin "3") (pinfunction "FB_3") (pintype "passive"))
    )
    (net (code "185") (name "Net-(UIO-INTA)") (class "Default")
      (node (ref "RI4") (pin "1") (pinfunction "1_1") (pintype "passive"))
      (node (ref "RI6") (pin "1") (pinfunction "1_1") (pintype "passive"))
      (node (ref "UIO") (pin "20") (pinfunction "INTA_20") (pintype "passive"))
    )
    (net (code "186") (name "Net-(UIO-INTB)") (class "Default")
      (node (ref "RI5") (pin "1") (pinfunction "1_1") (pintype "passive"))
      (node (ref "RI7") (pin "1") (pinfunction "1_1") (pintype "passive"))
      (node (ref "UIO") (pin "19") (pinfunction "INTB_19") (pintype "passive"))
    )
    (net (code "187") (name "Net-(UIO-RST)") (class "Default")
      (node (ref "RI1") (pin "1") (pinfunction "1_1") (pintype "passive"))
      (node (ref "UIO") (pin "18") (pinfunction "RST_18") (pintype "passive"))
    )
    (net (code "188") (name "Net-(UIO-SCL)") (class "Default")
      (node (ref "RI2") (pin "1") (pinfunction "1_1") (pintype "passive"))
      (node (ref "RI8") (pin "2") (pinfunction "2_2") (pintype "passive"))
      (node (ref "UIO") (pin "12") (pinfunction "SCL_12") (pintype "passive"))
    )
    (net (code "189") (name "Net-(UIO-SDA)") (class "Default")
      (node (ref "RI3") (pin "1") (pinfunction "1_1") (pintype "passive"))
      (node (ref "RI9") (pin "2") (pinfunction "2_2") (pintype "passive"))
      (node (ref "UIO") (pin "13") (pinfunction "SDA_13") (pintype "passive"))
    )
    (net (code "190") (name "V5") (class "Default")
      (node (ref "CI1") (pin "2") (pinfunction "2_2") (pintype "passive"))
      (node (ref "ESD1") (pin "5") (pinfunction "REF_5") (pintype "passive"))
      (node (ref "ESD2") (pin "5") (pinfunction "REF_5") (pintype "passive"))
      (node (ref "ESD3") (pin "5") (pinfunction "REF_5") (pintype "passive"))
      (node (ref "ESD4") (pin "5") (pinfunction "REF_5") (pintype "passive"))
      (node (ref "RA8") (pin "2") (pinfunction "2_2") (pintype "passive"))
      (node (ref "RI1") (pin "2") (pinfunction "2_2") (pintype "passive"))
      (node (ref "RI2") (pin "2") (pinfunction "2_2") (pintype "passive"))
      (node (ref "RI3") (pin "2") (pinfunction "2_2") (pintype "passive"))
      (node (ref "R_J5V") (pin "1") (pinfunction "1_1") (pintype "passive"))
      (node (ref "TVS") (pin "2") (pinfunction "K_2") (pintype "passive"))
      (node (ref "UIO") (pin "9") (pinfunction "VDD_9") (pintype "passive"))
    )
    (net (code "191") (name "V12") (class "Default")
      (node (ref "CQ19") (pin "1") (pinfunction "1_1") (pintype "passive"))
      (node (ref "CQ20") (pin "2") (pintype "passive"))
      (node (ref "CU24") (pin "1") (pinfunction "1_1") (pintype "passive"))
      (node (ref "RB8") (pin "2") (pinfunction "2_2") (pintype "passive"))
      (node (ref "U24") (pin "6") (pinfunction "VDD_6") (pintype "passive"))
    )
    (net (code "192") (name "V24") (class "Default")
      (node (ref "C1-2") (pin "1") (pintype "passive"))
      (node (ref "C11-12") (pin "1") (pintype "passive"))
      (node (ref "C13-14") (pin "1") (pintype "passive"))
      (node (ref "C15-16") (pin "1") (pintype "passive"))
      (node (ref "C17-18") (pin "1") (pintype "passive"))
      (node (ref "C3-4") (pin "1") (pintype "passive"))
      (node (ref "C5-6") (pin "1") (pintype "passive"))
      (node (ref "C7-8") (pin "1") (pintype "passive"))
      (node (ref "C9-10") (pin "1") (pintype "passive"))
      (node (ref "CA3") (pin "2") (pinfunction "2_2") (pintype "passive"))
      (node (ref "CB3") (pin "2") (pinfunction "2_2") (pintype "passive"))
      (node (ref "CU1-2") (pin "1") (pinfunction "1_1") (pintype "passive"))
      (node (ref "CU11-12") (pin "1") (pinfunction "1_1") (pintype "passive"))
      (node (ref "CU13-14") (pin "1") (pinfunction "1_1") (pintype "passive"))
      (node (ref "CU15-16") (pin "1") (pinfunction "1_1") (pintype "passive"))
      (node (ref "CU17-18") (pin "1") (pinfunction "1_1") (pintype "passive"))
      (node (ref "CU3-4") (pin "1") (pinfunction "1_1") (pintype "passive"))
      (node (ref "CU5-6") (pin "1") (pinfunction "1_1") (pintype "passive"))
      (node (ref "CU7-8") (pin "1") (pinfunction "1_1") (pintype "passive"))
      (node (ref "CU9-10") (pin "1") (pinfunction "1_1") (pintype "passive"))
      (node (ref "P24_O") (pin "3") (pinfunction "3_3") (pintype "passive"))
      (node (ref "P24_O") (pin "4") (pinfunction "4_4") (pintype "passive"))
      (node (ref "PWR") (pin "2") (pinfunction "2_2") (pintype "passive"))
      (node (ref "R1-2") (pin "1") (pinfunction "1_1") (pintype "passive"))
      (node (ref "R11-12") (pin "1") (pinfunction "1_1") (pintype "passive"))
      (node (ref "R13-14") (pin "1") (pinfunction "1_1") (pintype "passive"))
      (node (ref "R15-16") (pin "1") (pinfunction "1_1") (pintype "passive"))
      (node (ref "R17-18") (pin "1") (pinfunction "1_1") (pintype "passive"))
      (node (ref "R3-4") (pin "1") (pinfunction "1_1") (pintype "passive"))
      (node (ref "R5-6") (pin "1") (pinfunction "1_1") (pintype "passive"))
      (node (ref "R7-8") (pin "1") (pinfunction "1_1") (pintype "passive"))
      (node (ref "R9-10") (pin "1") (pinfunction "1_1") (pintype "passive"))
      (node (ref "RA1") (pin "2") (pinfunction "2_2") (pintype "passive"))
      (node (ref "RB1") (pin "2") (pinfunction "2_2") (pintype "passive"))
      (node (ref "RL_19") (pin "2") (pinfunction "2_2") (pintype "passive"))
      (node (ref "RL_20") (pin "2") (pinfunction "2_2") (pintype "passive"))
      (node (ref "RQ1") (pin "2") (pinfunction "2_2") (pintype "passive"))
      (node (ref "RQ10") (pin "1") (pinfunction "1_1") (pintype "passive"))
      (node (ref "RQ11") (pin "2") (pinfunction "2_2") (pintype "passive"))
      (node (ref "RQ12") (pin "1") (pinfunction "1_1") (pintype "passive"))
      (node (ref "RQ13") (pin "2") (pinfunction "2_2") (pintype "passive"))
      (node (ref "RQ14") (pin "1") (pinfunction "1_1") (pintype "passive"))
      (node (ref "RQ15") (pin "2") (pinfunction "2_2") (pintype "passive"))
      (node (ref "RQ16") (pin "1") (pinfunction "1_1") (pintype "passive"))
      (node (ref "RQ17") (pin "2") (pinfunction "2_2") (pintype "passive"))
      (node (ref "RQ18") (pin "1") (pinfunction "1_1") (pintype "passive"))
      (node (ref "RQ2") (pin "1") (pinfunction "1_1") (pintype "passive"))
      (node (ref "RQ3") (pin "2") (pinfunction "2_2") (pintype "passive"))
      (node (ref "RQ4") (pin "1") (pinfunction "1_1") (pintype "passive"))
      (node (ref "RQ5") (pin "2") (pinfunction "2_2") (pintype "passive"))
      (node (ref "RQ6") (pin "1") (pinfunction "1_1") (pintype "passive"))
      (node (ref "RQ7") (pin "2") (pinfunction "2_2") (pintype "passive"))
      (node (ref "RQ8") (pin "1") (pinfunction "1_1") (pintype "passive"))
      (node (ref "RQ9") (pin "2") (pinfunction "2_2") (pintype "passive"))
      (node (ref "U-05") (pin "5") (pinfunction "VIN_5") (pintype "passive"))
      (node (ref "U-12") (pin "5") (pinfunction "VIN_5") (pintype "passive"))
      (node (ref "U1-2") (pin "6") (pinfunction "VS_6") (pintype "passive"))
      (node (ref "U11-12") (pin "6") (pinfunction "VS_6") (pintype "passive"))
      (node (ref "U13-14") (pin "6") (pinfunction "VS_6") (pintype "passive"))
      (node (ref "U15-16") (pin "6") (pinfunction "VS_6") (pintype "passive"))
      (node (ref "U17-18") (pin "6") (pinfunction "VS_6") (pintype "passive"))
      (node (ref "U3-4") (pin "6") (pinfunction "VS_6") (pintype "passive"))
      (node (ref "U5-6") (pin "6") (pinfunction "VS_6") (pintype "passive"))
      (node (ref "U7-8") (pin "6") (pinfunction "VS_6") (pintype "passive"))
      (node (ref "U9-10") (pin "6") (pinfunction "VS_6") (pintype "passive"))
    )
    (net (code "193") (name "VG_R") (class "Default")
      (node (ref "C00") (pin "1") (pinfunction "1_1") (pintype "passive"))
      (node (ref "C02") (pin "1") (pinfunction "1_1") (pintype "passive"))
      (node (ref "C03") (pin "1") (pinfunction "1_1") (pintype "passive"))
      (node (ref "C04") (pin "1") (pinfunction "1_1") (pintype "passive"))
      (node (ref "C05") (pin "1") (pinfunction "1_1") (pintype "passive"))
      (node (ref "C06") (pin "1") (pinfunction "1_1") (pintype "passive"))
      (node (ref "C07") (pin "1") (pinfunction "1_1") (pintype "passive"))
      (node (ref "C08") (pin "1") (pinfunction "1_1") (pintype "passive"))
      (node (ref "C09") (pin "1") (pinfunction "1_1") (pintype "passive"))
      (node (ref "C1-2") (pin "2") (pintype "passive"))
      (node (ref "C10") (pin "1") (pinfunction "1_1") (pintype "passive"))
      (node (ref "C11") (pin "1") (pinfunction "1_1") (pintype "passive"))
      (node (ref "C11-12") (pin "2") (pintype "passive"))
      (node (ref "C12") (pin "1") (pinfunction "1_1") (pintype "passive"))
      (node (ref "C13") (pin "1") (pinfunction "1_1") (pintype "passive"))
      (node (ref "C13-14") (pin "2") (pintype "passive"))
      (node (ref "C14") (pin "1") (pinfunction "1_1") (pintype "passive"))
      (node (ref "C15") (pin "1") (pinfunction "1_1") (pintype "passive"))
      (node (ref "C15-16") (pin "2") (pintype "passive"))
      (node (ref "C16") (pin "1") (pinfunction "1_1") (pintype "passive"))
      (node (ref "C17-18") (pin "2") (pintype "passive"))
      (node (ref "C3-4") (pin "2") (pintype "passive"))
      (node (ref "C5-6") (pin "2") (pintype "passive"))
      (node (ref "C7-8") (pin "2") (pintype "passive"))
      (node (ref "C9-10") (pin "2") (pintype "passive"))
      (node (ref "CA3") (pin "1") (pinfunction "1_1") (pintype "passive"))
      (node (ref "CA4") (pin "2") (pinfunction "2_2") (pintype "passive"))
      (node (ref "CB3") (pin "1") (pinfunction "1_1") (pintype "passive"))
      (node (ref "CB4") (pin "2") (pinfunction "2_2") (pintype "passive"))
      (node (ref "CI1") (pin "1") (pinfunction "1_1") (pintype "passive"))
      (node (ref "CQ1") (pin "2") (pintype "passive"))
      (node (ref "CQ10") (pin "2") (pintype "passive"))
      (node (ref "CQ11") (pin "2") (pintype "passive"))
      (node (ref "CQ12") (pin "2") (pintype "passive"))
      (node (ref "CQ13") (pin "2") (pintype "passive"))
      (node (ref "CQ14") (pin "2") (pintype "passive"))
      (node (ref "CQ15") (pin "2") (pintype "passive"))
      (node (ref "CQ16") (pin "2") (pintype "passive"))
      (node (ref "CQ17") (pin "2") (pintype "passive"))
      (node (ref "CQ18") (pin "2") (pintype "passive"))
      (node (ref "CQ19") (pin "2") (pinfunction "2_2") (pintype "passive"))
      (node (ref "CQ2") (pin "2") (pintype "passive"))
      (node (ref "CQ20") (pin "1") (pintype "passive"))
      (node (ref "CQ3") (pin "2") (pintype "passive"))
      (node (ref "CQ4") (pin "2") (pintype "passive"))
      (node (ref "CQ5") (pin "2") (pintype "passive"))
      (node (ref "CQ6") (pin "2") (pintype "passive"))
      (node (ref "CQ7") (pin "2") (pintype "passive"))
      (node (ref "CQ8") (pin "2") (pintype "passive"))
      (node (ref "CQ9") (pin "2") (pintype "passive"))
      (node (ref "CU1-2") (pin "2") (pinfunction "2_2") (pintype "passive"))
      (node (ref "CU11-12") (pin "2") (pinfunction "2_2") (pintype "passive"))
      (node (ref "CU13-14") (pin "2") (pinfunction "2_2") (pintype "passive"))
      (node (ref "CU15-16") (pin "2") (pinfunction "2_2") (pintype "passive"))
      (node (ref "CU17-18") (pin "2") (pinfunction "2_2") (pintype "passive"))
      (node (ref "CU24") (pin "2") (pinfunction "2_2") (pintype "passive"))
      (node (ref "CU3-4") (pin "2") (pinfunction "2_2") (pintype "passive"))
      (node (ref "CU5-6") (pin "2") (pinfunction "2_2") (pintype "passive"))
      (node (ref "CU7-8") (pin "2") (pinfunction "2_2") (pintype "passive"))
      (node (ref "CU9-10") (pin "2") (pinfunction "2_2") (pintype "passive"))
      (node (ref "D1-2") (pin "1") (pinfunction "A_1") (pintype "passive"))
      (node (ref "D11-12") (pin "1") (pinfunction "A_1") (pintype "passive"))
      (node (ref "D13-14") (pin "1") (pinfunction "A_1") (pintype "passive"))
      (node (ref "D15-16") (pin "1") (pinfunction "A_1") (pintype "passive"))
      (node (ref "D17-18") (pin "1") (pinfunction "A_1") (pintype "passive"))
      (node (ref "D3-4") (pin "1") (pinfunction "A_1") (pintype "passive"))
      (node (ref "D5-6") (pin "1") (pinfunction "A_1") (pintype "passive"))
      (node (ref "D7-8") (pin "1") (pinfunction "A_1") (pintype "passive"))
      (node (ref "D9-10") (pin "1") (pinfunction "A_1") (pintype "passive"))
      (node (ref "DX_1") (pin "1") (pintype "passive"))
      (node (ref "DX_10") (pin "1") (pintype "passive"))
      (node (ref "DX_11") (pin "1") (pintype "passive"))
      (node (ref "DX_12") (pin "1") (pintype "passive"))
      (node (ref "DX_13") (pin "1") (pintype "passive"))
      (node (ref "DX_14") (pin "1") (pintype "passive"))
      (node (ref "DX_15") (pin "1") (pintype "passive"))
      (node (ref "DX_16") (pin "1") (pintype "passive"))
      (node (ref "DX_17") (pin "1") (pintype "passive"))
      (node (ref "DX_18") (pin "1") (pintype "passive"))
      (node (ref "DX_2") (pin "1") (pintype "passive"))
      (node (ref "DX_3") (pin "1") (pintype "passive"))
      (node (ref "DX_4") (pin "1") (pintype "passive"))
      (node (ref "DX_5") (pin "1") (pintype "passive"))
      (node (ref "DX_6") (pin "1") (pintype "passive"))
      (node (ref "DX_7") (pin "1") (pintype "passive"))
      (node (ref "DX_8") (pin "1") (pintype "passive"))
      (node (ref "DX_9") (pin "1") (pintype "passive"))
      (node (ref "ESD1") (pin "2") (pinfunction "GND_2") (pintype "passive"))
      (node (ref "ESD2") (pin "2") (pinfunction "GND_2") (pintype "passive"))
      (node (ref "ESD3") (pin "2") (pinfunction "GND_2") (pintype "passive"))
      (node (ref "ESD4") (pin "2") (pinfunction "GND_2") (pintype "passive"))
      (node (ref "JR") (pin "24") (pinfunction "24_24") (pintype "passive"))
      (node (ref "LED_01") (pin "K") (pintype "passive"))
      (node (ref "LED_02") (pin "K") (pintype "passive"))
      (node (ref "LED_03") (pin "K") (pintype "passive"))
      (node (ref "LED_04") (pin "K") (pintype "passive"))
      (node (ref "LED_05") (pin "K") (pintype "passive"))
      (node (ref "LED_06") (pin "K") (pintype "passive"))
      (node (ref "LED_07") (pin "K") (pintype "passive"))
      (node (ref "LED_08") (pin "K") (pintype "passive"))
      (node (ref "LED_09") (pin "K") (pintype "passive"))
      (node (ref "LED_10") (pin "K") (pintype "passive"))
      (node (ref "LED_11") (pin "K") (pintype "passive"))
      (node (ref "LED_12") (pin "K") (pintype "passive"))
      (node (ref "LED_13") (pin "K") (pintype "passive"))
      (node (ref "LED_14") (pin "K") (pintype "passive"))
      (node (ref "LED_15") (pin "K") (pintype "passive"))
      (node (ref "LED_16") (pin "K") (pintype "passive"))
      (node (ref "LED_17") (pin "K") (pintype "passive"))
      (node (ref "LED_18") (pin "K") (pintype "passive"))
      (node (ref "P24_O") (pin "1") (pinfunction "1_1") (pintype "passive"))
      (node (ref "P24_O") (pin "2") (pinfunction "2_2") (pintype "passive"))
      (node (ref "PWR") (pin "1") (pinfunction "1_1") (pintype "passive"))
      (node (ref "QP19") (pin "3") (pinfunction "S_3") (pintype "passive"))
      (node (ref "QP20") (pin "3") (pinfunction "S_3") (pintype "passive"))
      (node (ref "R11") (pin "1") (pinfunction "1_1") (pintype "passive"))
      (node (ref "R14") (pin "1") (pinfunction "1_1") (pintype "passive"))
      (node (ref "R17") (pin "1") (pinfunction "1_1") (pintype "passive"))
      (node (ref "R2") (pin "1") (pinfunction "1_1") (pintype "passive"))
      (node (ref "R20") (pin "1") (pinfunction "1_1") (pintype "passive"))
      (node (ref "R23") (pin "1") (pinfunction "1_1") (pintype "passive"))
      (node (ref "R26") (pin "1") (pinfunction "1_1") (pintype "passive"))
      (node (ref "R29") (pin "1") (pinfunction "1_1") (pintype "passive"))
      (node (ref "R32") (pin "1") (pinfunction "1_1") (pintype "passive"))
      (node (ref "R35") (pin "1") (pinfunction "1_1") (pintype "passive"))
      (node (ref "R38") (pin "1") (pinfunction "1_1") (pintype "passive"))
      (node (ref "R41") (pin "1") (pinfunction "1_1") (pintype "passive"))
      (node (ref "R44") (pin "1") (pinfunction "1_1") (pintype "passive"))
      (node (ref "R47") (pin "1") (pinfunction "1_1") (pintype "passive"))
      (node (ref "R5") (pin "1") (pinfunction "1_1") (pintype "passive"))
      (node (ref "R8") (pin "1") (pinfunction "1_1") (pintype "passive"))
      (node (ref "RA7") (pin "2") (pinfunction "2_2") (pintype "passive"))
      (node (ref "RB7") (pin "2") (pinfunction "2_2") (pintype "passive"))
      (node (ref "RI4") (pin "2") (pinfunction "2_2") (pintype "passive"))
      (node (ref "RI5") (pin "2") (pinfunction "2_2") (pintype "passive"))
      (node (ref "RP1-4") (pin "5") (pinfunction "5_5") (pintype "passive"))
      (node (ref "RP1-4") (pin "6") (pinfunction "6_6") (pintype "passive"))
      (node (ref "RP1-4") (pin "7") (pinfunction "7_7") (pintype "passive"))
      (node (ref "RP1-4") (pin "8") (pinfunction "8_8") (pintype "passive"))
      (node (ref "RP13-16") (pin "5") (pinfunction "5_5") (pintype "passive"))
      (node (ref "RP13-16") (pin "6") (pinfunction "6_6") (pintype "passive"))
      (node (ref "RP13-16") (pin "7") (pinfunction "7_7") (pintype "passive"))
      (node (ref "RP13-16") (pin "8") (pinfunction "8_8") (pintype "passive"))
      (node (ref "RP17-20") (pin "5") (pinfunction "5_5") (pintype "passive"))
      (node (ref "RP17-20") (pin "6") (pinfunction "6_6") (pintype "passive"))
      (node (ref "RP17-20") (pin "7") (pinfunction "7_7") (pintype "passive"))
      (node (ref "RP17-20") (pin "8") (pinfunction "8_8") (pintype "passive"))
      (node (ref "RP5-8") (pin "5") (pinfunction "5_5") (pintype "passive"))
      (node (ref "RP5-8") (pin "6") (pinfunction "6_6") (pintype "passive"))
      (node (ref "RP5-8") (pin "7") (pinfunction "7_7") (pintype "passive"))
      (node (ref "RP5-8") (pin "8") (pinfunction "8_8") (pintype "passive"))
      (node (ref "RP9-12") (pin "5") (pinfunction "5_5") (pintype "passive"))
      (node (ref "RP9-12") (pin "6") (pinfunction "6_6") (pintype "passive"))
      (node (ref "RP9-12") (pin "7") (pinfunction "7_7") (pintype "passive"))
      (node (ref "RP9-12") (pin "8") (pinfunction "8_8") (pintype "passive"))
      (node (ref "SA1") (pin "1") (pinfunction "A_1") (pintype "passive"))
      (node (ref "SB1") (pin "1") (pinfunction "A_1") (pintype "passive"))
      (node (ref "TVS") (pin "1") (pinfunction "A_1") (pintype "passive"))
      (node (ref "U-05") (pin "2") (pinfunction "GND_2") (pintype "passive"))
      (node (ref "U-12") (pin "2") (pinfunction "GND_2") (pintype "passive"))
      (node (ref "U1-2") (pin "3") (pinfunction "GND_3") (pintype "passive"))
      (node (ref "U11-12") (pin "3") (pinfunction "GND_3") (pintype "passive"))
      (node (ref "U13-14") (pin "3") (pinfunction "GND_3") (pintype "passive"))
      (node (ref "U15-16") (pin "3") (pinfunction "GND_3") (pintype "passive"))
      (node (ref "U17-18") (pin "3") (pinfunction "GND_3") (pintype "passive"))
      (node (ref "U24") (pin "3") (pinfunction "GND_3") (pintype "passive"))
      (node (ref "U3-4") (pin "3") (pinfunction "GND_3") (pintype "passive"))
      (node (ref "U5-6") (pin "3") (pinfunction "GND_3") (pintype "passive"))
      (node (ref "U7-8") (pin "3") (pinfunction "GND_3") (pintype "passive"))
      (node (ref "U9-10") (pin "3") (pinfunction "GND_3") (pintype "passive"))
      (node (ref "UIO") (pin "10") (pinfunction "VSS_10") (pintype "passive"))
      (node (ref "UIO") (pin "15") (pinfunction "A0_15") (pintype "passive"))
      (node (ref "UIO") (pin "16") (pinfunction "A1_16") (pintype "passive"))
      (node (ref "UIO") (pin "17") (pinfunction "A2_17") (pintype "passive"))
      (node (ref "ZD19") (pin "1") (pintype "passive"))
      (node (ref "ZD20") (pin "1") (pintype "passive"))
      (node (ref "ZM01") (pin "1") (pinfunction "A_1") (pintype "passive"))
      (node (ref "ZM02") (pin "1") (pinfunction "A_1") (pintype "passive"))
      (node (ref "ZM03") (pin "1") (pinfunction "A_1") (pintype "passive"))
      (node (ref "ZM04") (pin "1") (pinfunction "A_1") (pintype "passive"))
      (node (ref "ZM05") (pin "1") (pinfunction "A_1") (pintype "passive"))
      (node (ref "ZM06") (pin "1") (pinfunction "A_1") (pintype "passive"))
      (node (ref "ZM07") (pin "1") (pinfunction "A_1") (pintype "passive"))
      (node (ref "ZM08") (pin "1") (pinfunction "A_1") (pintype "passive"))
      (node (ref "ZM09") (pin "1") (pinfunction "A_1") (pintype "passive"))
      (node (ref "ZM10") (pin "1") (pinfunction "A_1") (pintype "passive"))
      (node (ref "ZM11") (pin "1") (pinfunction "A_1") (pintype "passive"))
      (node (ref "ZM12") (pin "1") (pinfunction "A_1") (pintype "passive"))
      (node (ref "ZM13") (pin "1") (pinfunction "A_1") (pintype "passive"))
      (node (ref "ZM14") (pin "1") (pinfunction "A_1") (pintype "passive"))
      (node (ref "ZM15") (pin "1") (pinfunction "A_1") (pintype "passive"))
      (node (ref "ZM16") (pin "1") (pinfunction "A_1") (pintype "passive"))
    )
    (net (code "194") (name "unconnected-(PWR-Pad3)") (class "Default")
      (node (ref "PWR") (pin "3") (pinfunction "3_3") (pintype "passive+no_connect"))
    )
    (net (code "195") (name "unconnected-(PWR-Pad4)") (class "Default")
      (node (ref "PWR") (pin "4") (pinfunction "4_4") (pintype "passive+no_connect"))
    )
    (net (code "196") (name "unconnected-(U24-NC-Pad1)") (class "Default")
      (node (ref "U24") (pin "1") (pinfunction "NC_1") (pintype "passive+no_connect"))
    )
    (net (code "197") (name "unconnected-(U24-NC-Pad8)") (class "Default")
      (node (ref "U24") (pin "8") (pinfunction "NC_8") (pintype "passive+no_connect"))
    )
    (net (code "198") (name "unconnected-(UIO-NC-Pad11)") (class "Default")
      (node (ref "UIO") (pin "11") (pinfunction "NC_11") (pintype "passive+no_connect"))
    )
    (net (code "199") (name "unconnected-(UIO-NC-Pad14)") (class "Default")
      (node (ref "UIO") (pin "14") (pinfunction "NC_14") (pintype "passive+no_connect"))
    )
  )
)
